# CrowPanel_Pico_Display-2_4_V1_0_240412.net
KiCad netlist of a schematic drawn in EAGLE
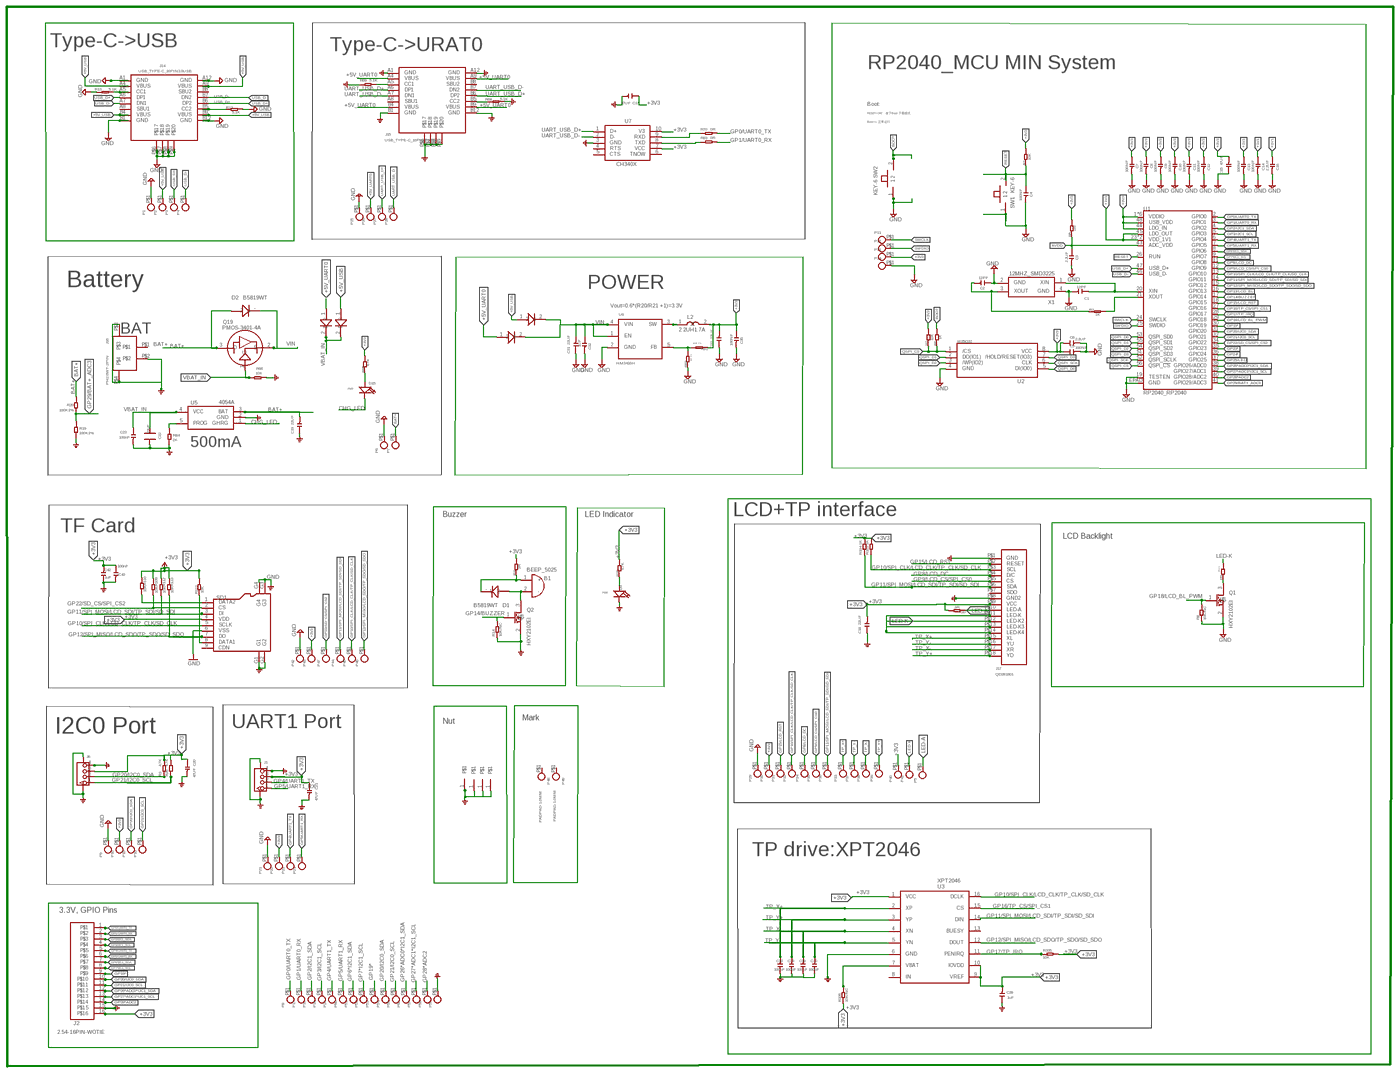
[diagram p0: schematic, sheet 1, overview]
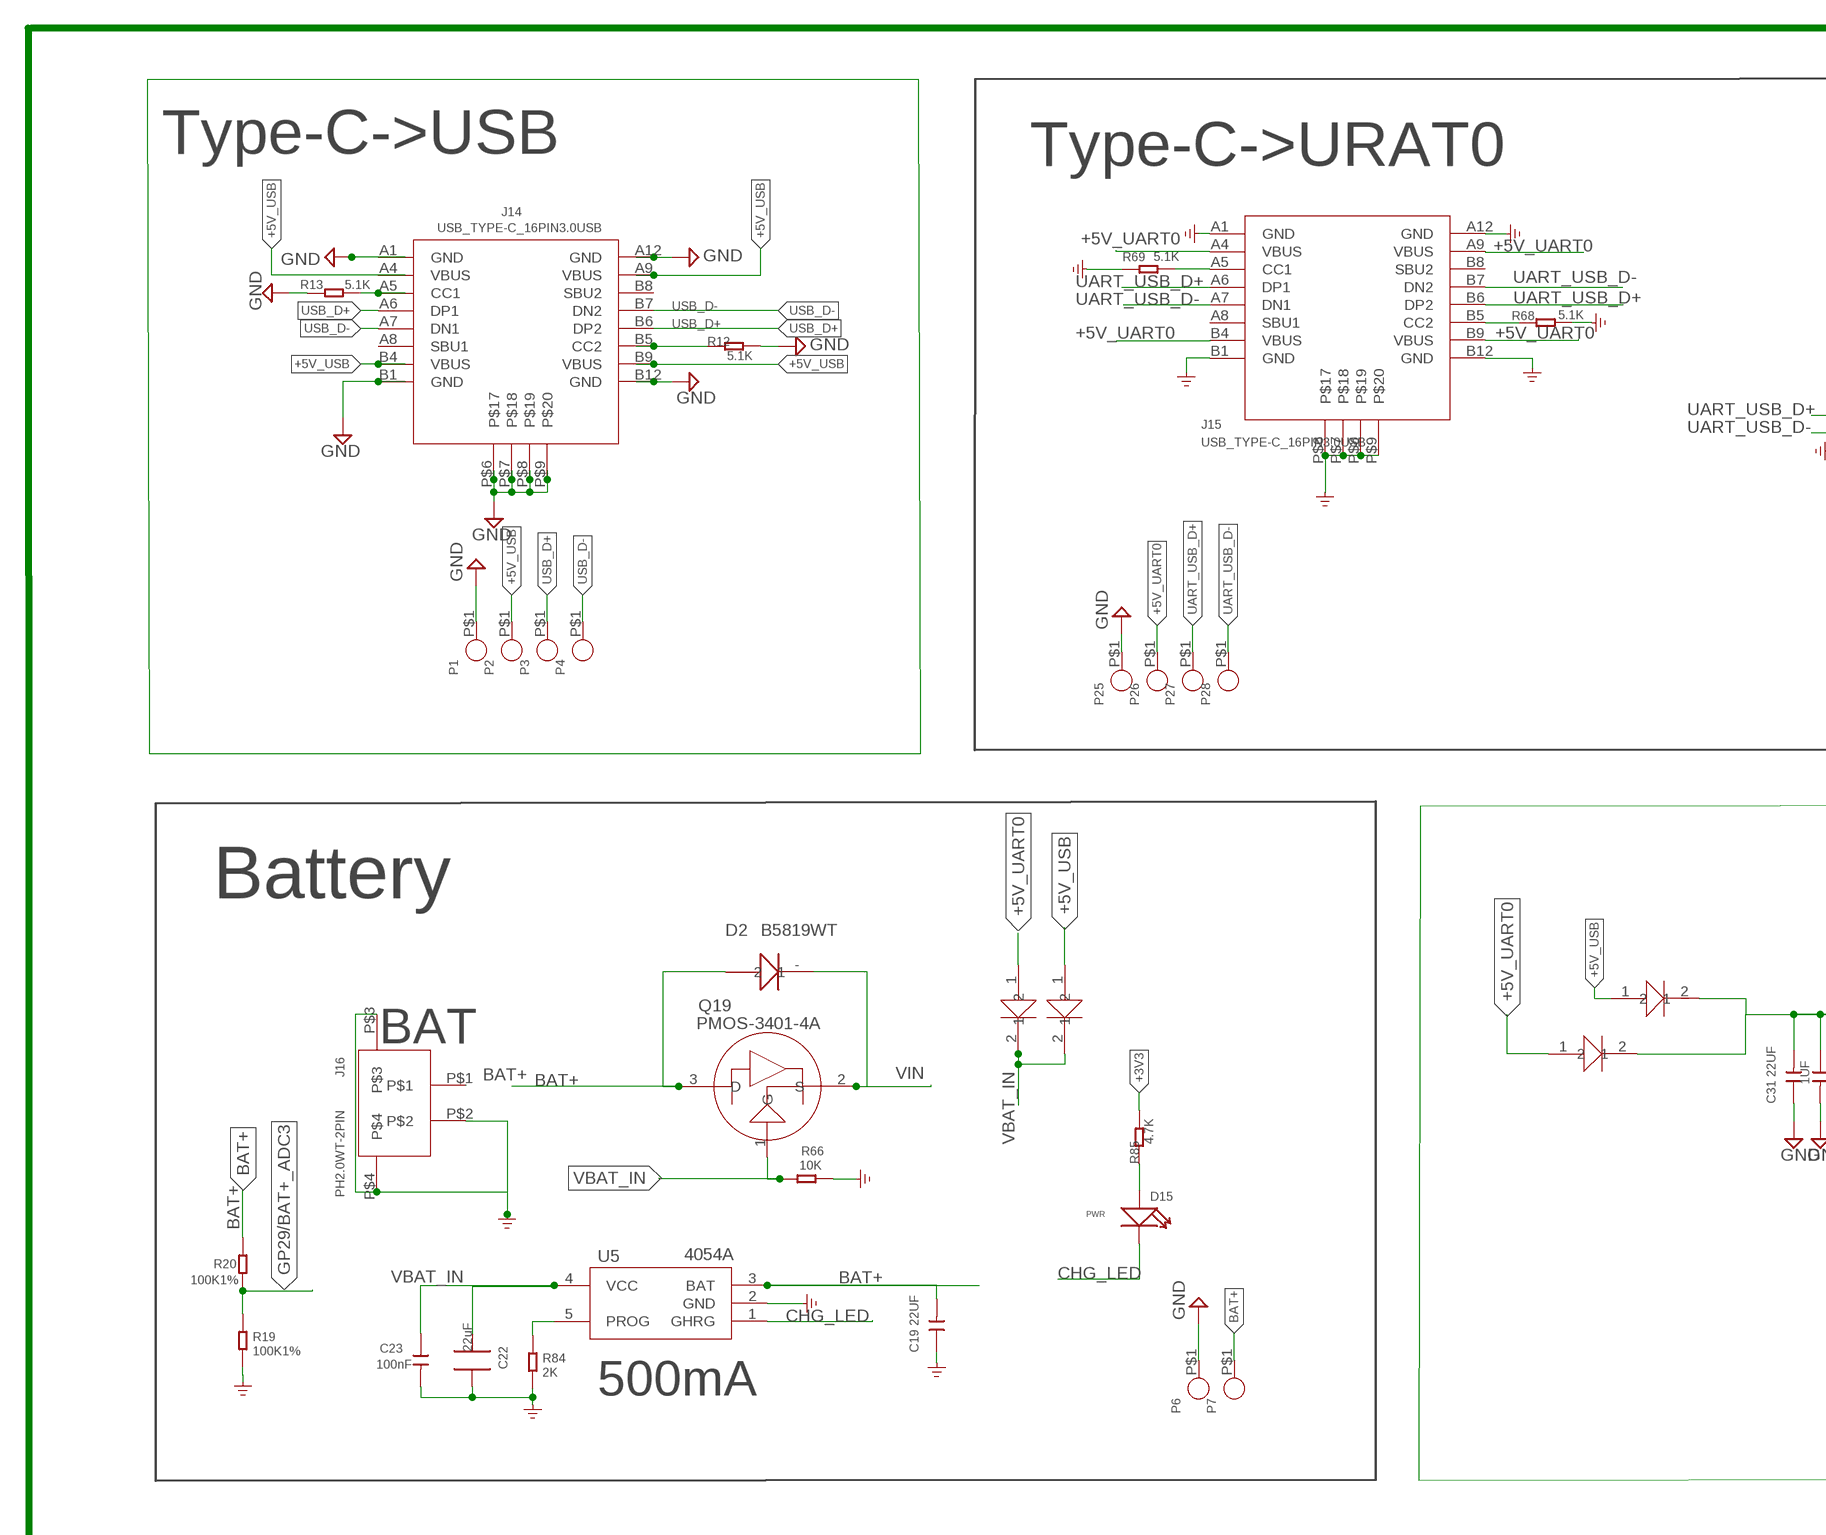
[diagram p1: schematic, sheet 1, part 1 of 4]
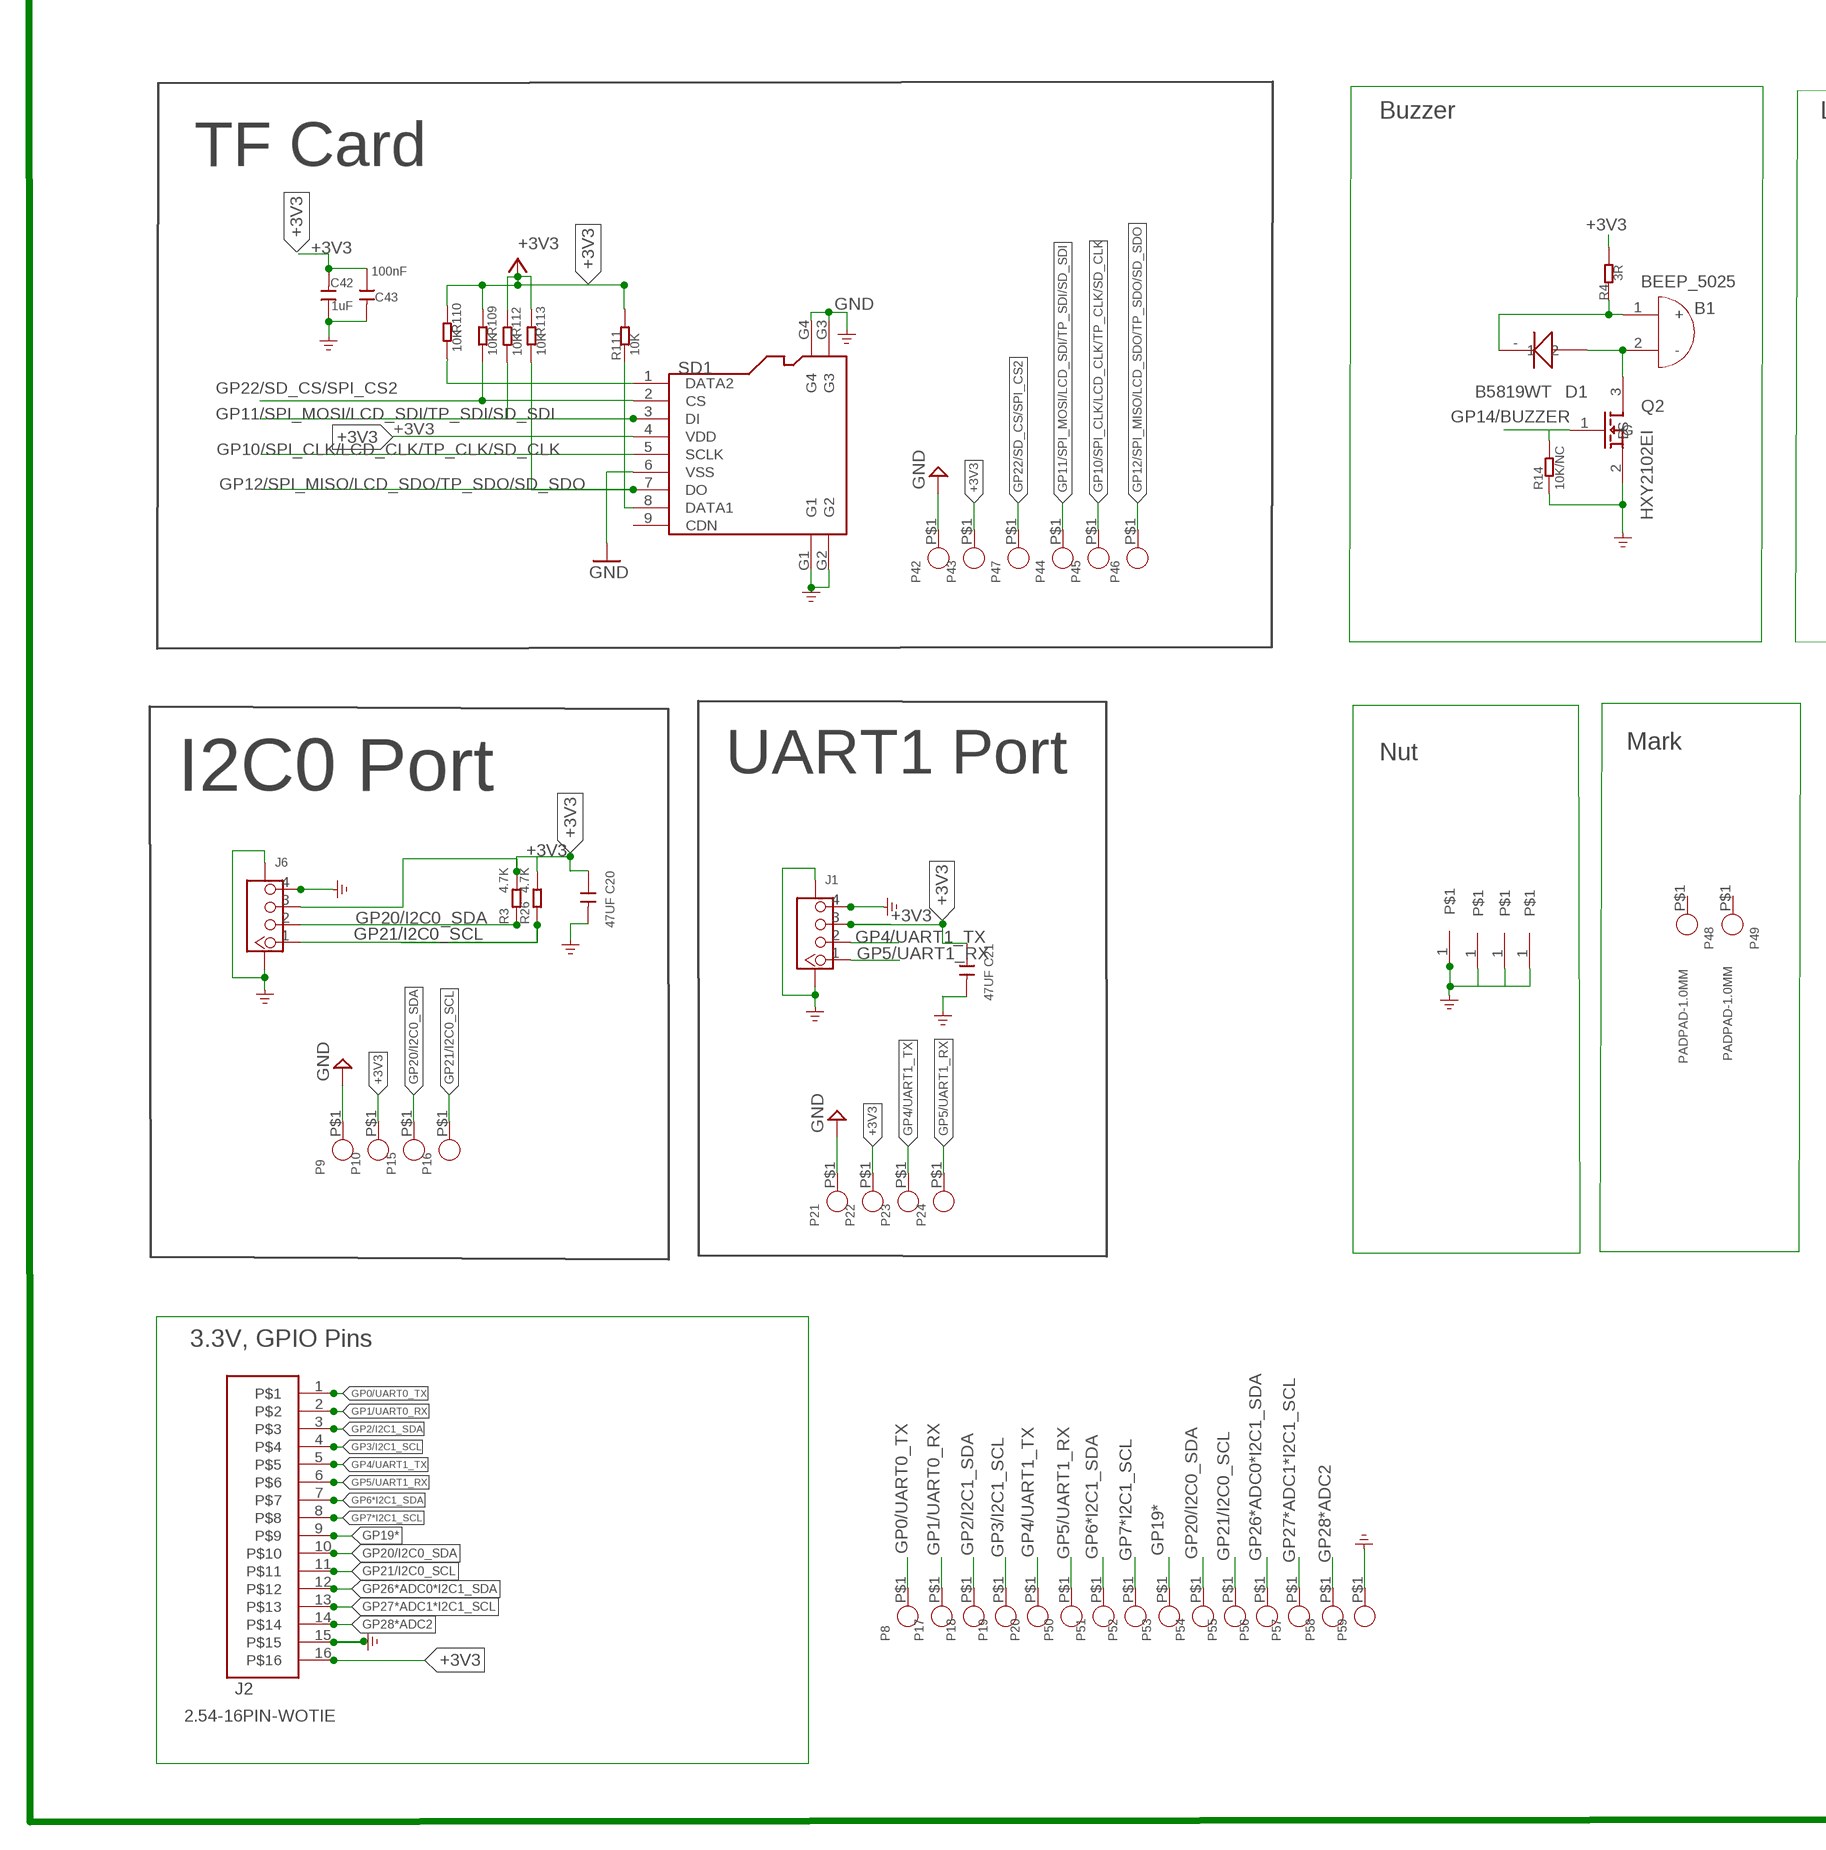
[diagram p2: schematic, sheet 1, part 2 of 4]
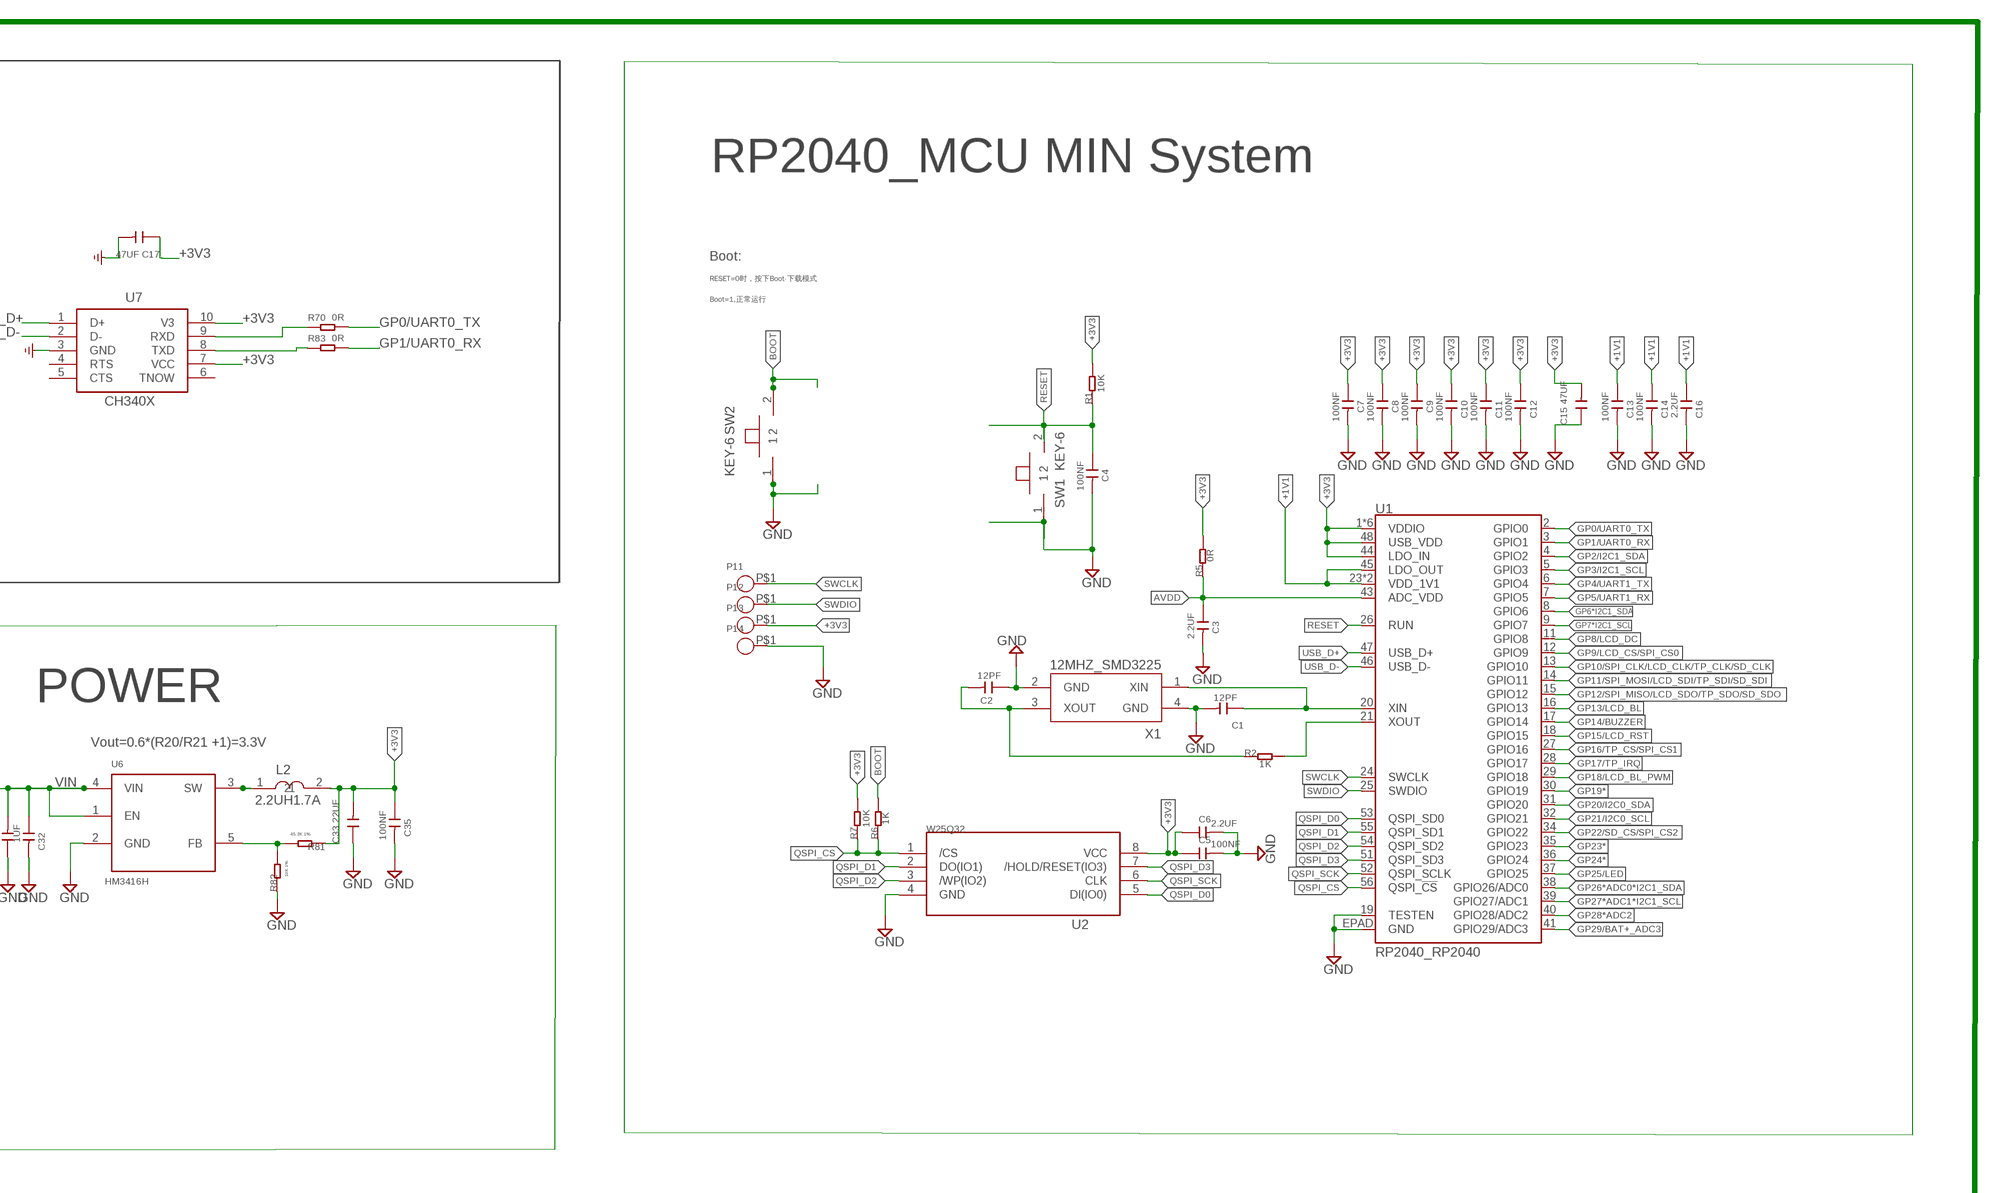
[diagram p3: schematic, sheet 1, part 3 of 4]
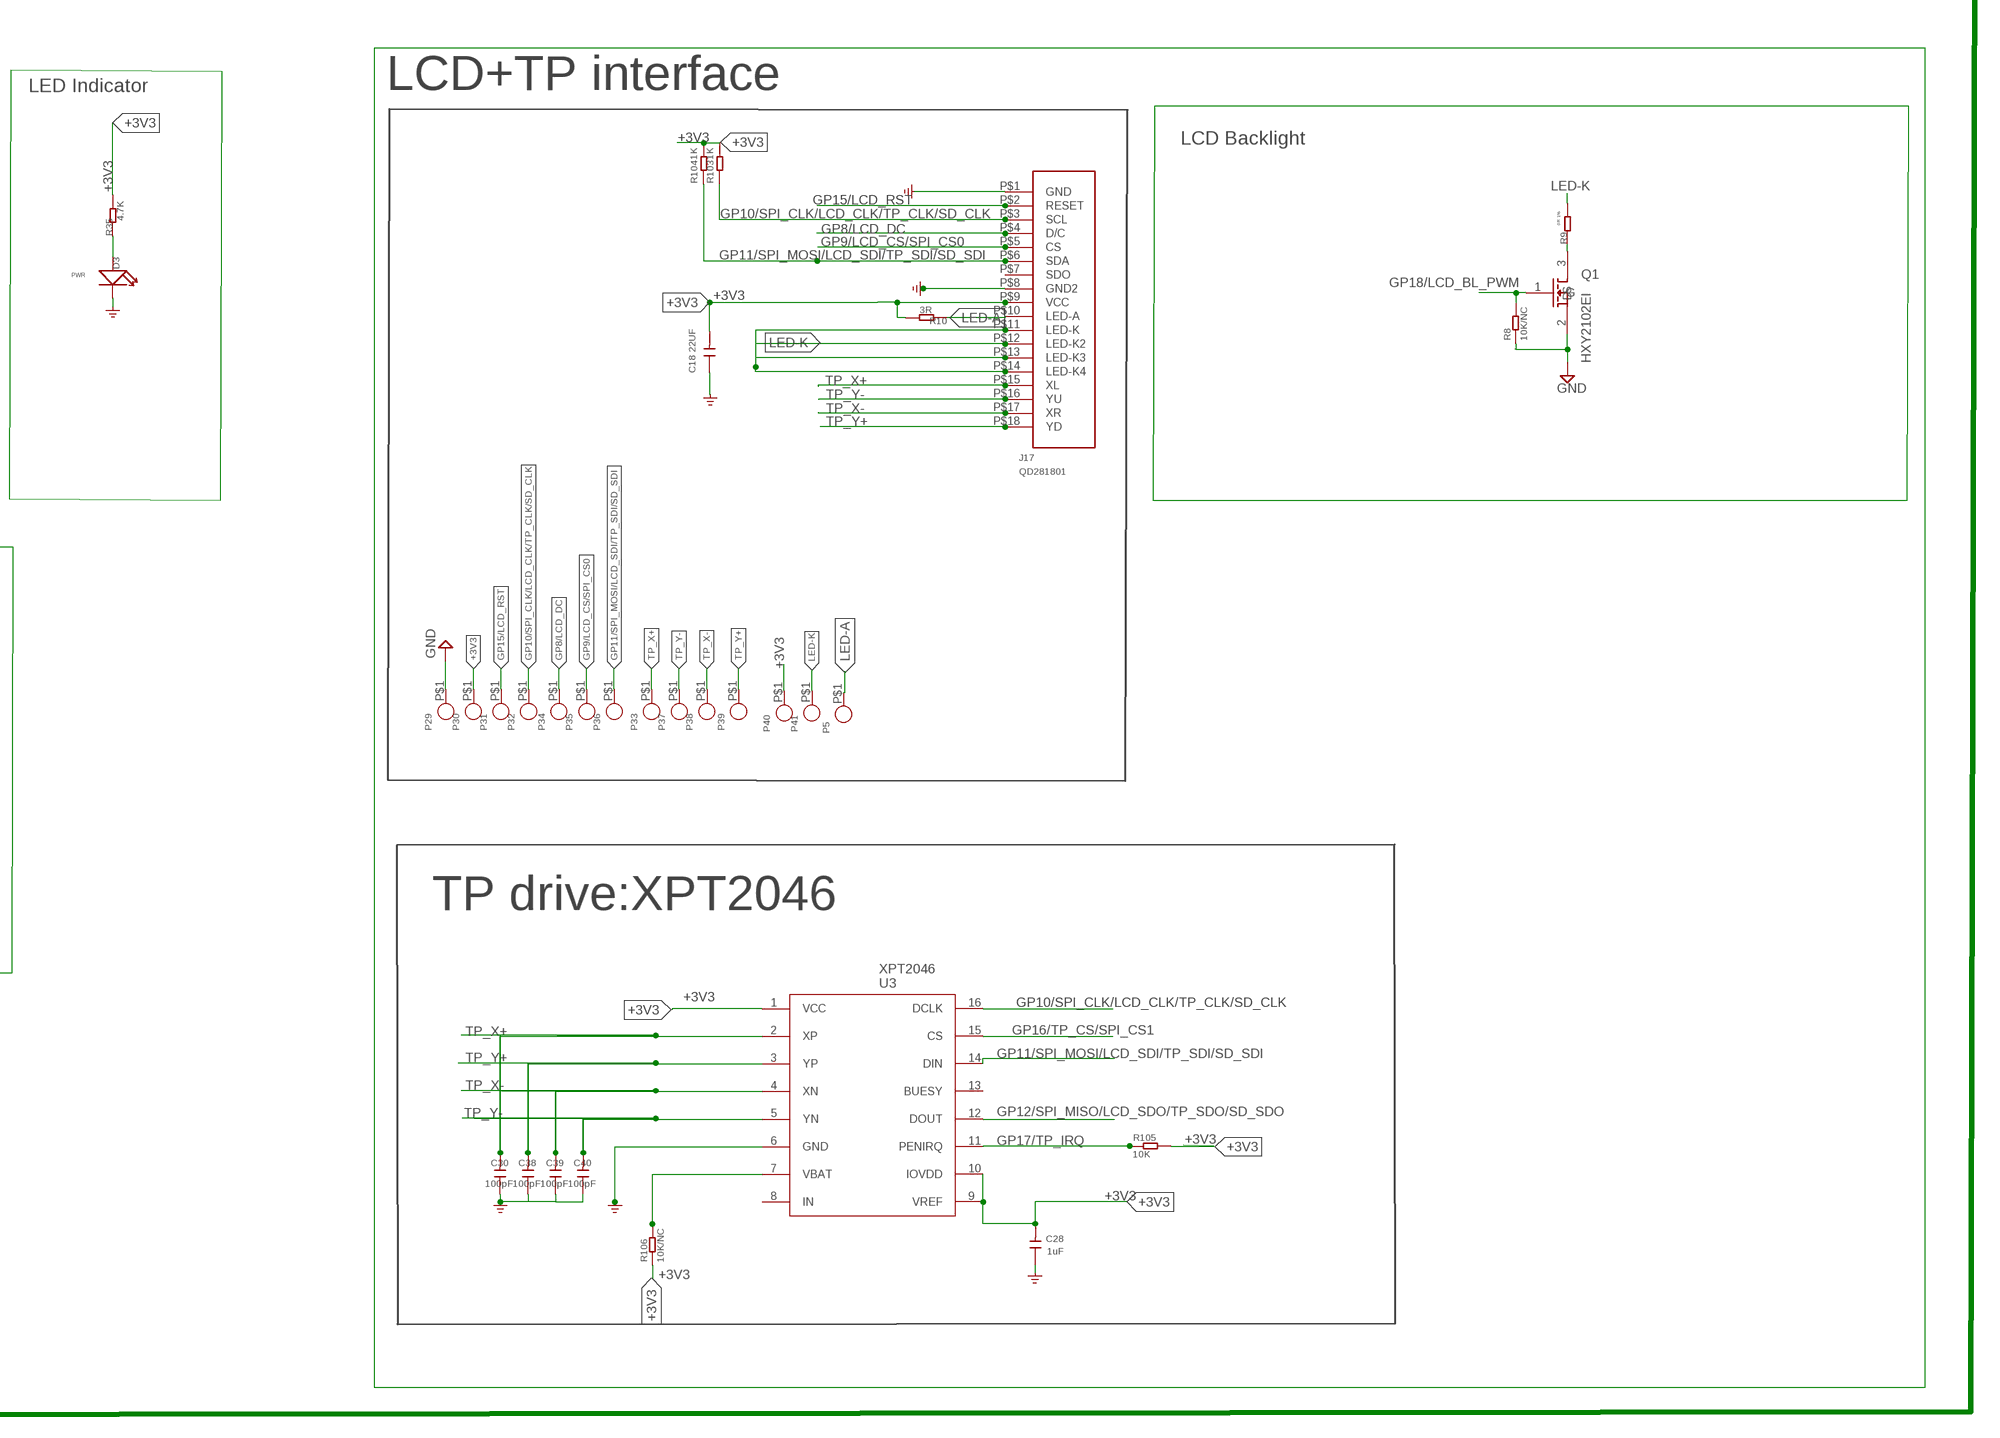
[diagram p4: schematic, sheet 1, part 4 of 4]

(export (version "E")
  (design (tool "Eeschema 10.0.6"))
  (components
    (comp (ref "B1")
      (value "BEEP_5025")
      (footprint "eagle-import:BEEP_5025")
      (libsource (lib "eagle-import") (part "BEEP_5025"))
    )
    (comp (ref "C1")
      (value "12PF")
      (footprint "eagle-import:A_XBJ_0603")
      (libsource (lib "eagle-import") (part "A_XBJ_C0603"))
    )
    (comp (ref "C2")
      (value "12PF")
      (footprint "eagle-import:A_XBJ_0603")
      (libsource (lib "eagle-import") (part "A_XBJ_C0603"))
    )
    (comp (ref "C3")
      (value "2.2UF")
      (footprint "eagle-import:A_XBJ_0603")
      (libsource (lib "eagle-import") (part "A_XBJ_C0603"))
    )
    (comp (ref "C4")
      (value "100NF")
      (footprint "eagle-import:A_XBJ_0603")
      (libsource (lib "eagle-import") (part "A_XBJ_C0603"))
    )
    (comp (ref "C5")
      (value "100NF")
      (footprint "eagle-import:A_XBJ_0603")
      (libsource (lib "eagle-import") (part "A_XBJ_C0603"))
    )
    (comp (ref "C6")
      (value "2.2UF")
      (footprint "eagle-import:A_XBJ_0603")
      (libsource (lib "eagle-import") (part "A_XBJ_C0603"))
    )
    (comp (ref "C7")
      (value "100NF")
      (footprint "eagle-import:A_XBJ_0603")
      (libsource (lib "eagle-import") (part "A_XBJ_C0603"))
    )
    (comp (ref "C8")
      (value "100NF")
      (footprint "eagle-import:A_XBJ_0603")
      (libsource (lib "eagle-import") (part "A_XBJ_C0603"))
    )
    (comp (ref "C9")
      (value "100NF")
      (footprint "eagle-import:A_XBJ_0603")
      (libsource (lib "eagle-import") (part "A_XBJ_C0603"))
    )
    (comp (ref "C10")
      (value "100NF")
      (footprint "eagle-import:A_XBJ_0603")
      (libsource (lib "eagle-import") (part "A_XBJ_C0603"))
    )
    (comp (ref "C11")
      (value "100NF")
      (footprint "eagle-import:A_XBJ_0603")
      (libsource (lib "eagle-import") (part "A_XBJ_C0603"))
    )
    (comp (ref "C12")
      (value "100NF")
      (footprint "eagle-import:A_XBJ_0603")
      (libsource (lib "eagle-import") (part "A_XBJ_C0603"))
    )
    (comp (ref "C13")
      (value "100NF")
      (footprint "eagle-import:A_XBJ_0603")
      (libsource (lib "eagle-import") (part "A_XBJ_C0603"))
    )
    (comp (ref "C14")
      (value "100NF")
      (footprint "eagle-import:A_XBJ_0603")
      (libsource (lib "eagle-import") (part "A_XBJ_C0603"))
    )
    (comp (ref "C15")
      (value "47UF")
      (footprint "eagle-import:A_XBJ_0805")
      (libsource (lib "eagle-import") (part "A_XBJ_C0805"))
    )
    (comp (ref "C16")
      (value "2.2UF")
      (footprint "eagle-import:A_XBJ_0603")
      (libsource (lib "eagle-import") (part "A_XBJ_C0603"))
    )
    (comp (ref "C17")
      (value "47UF")
      (footprint "eagle-import:A_XBJ_0805")
      (libsource (lib "eagle-import") (part "A_XBJ_C0805"))
    )
    (comp (ref "C18")
      (value "22UF")
      (footprint "eagle-import:A_XBJ_0805")
      (libsource (lib "eagle-import") (part "A_XBJ_C0805"))
    )
    (comp (ref "C19")
      (value "22UF")
      (footprint "eagle-import:A_XBJ_0805")
      (libsource (lib "eagle-import") (part "A_XBJ_C0805"))
    )
    (comp (ref "C20")
      (value "47UF")
      (footprint "eagle-import:A_XBJ_0805")
      (libsource (lib "eagle-import") (part "A_XBJ_C0805"))
    )
    (comp (ref "C21")
      (value "47UF")
      (footprint "eagle-import:A_XBJ_0805")
      (libsource (lib "eagle-import") (part "A_XBJ_C0805"))
    )
    (comp (ref "C22")
      (value "22uF")
      (footprint "eagle-import:0805_S")
      (libsource (lib "eagle-import") (part "C0805_S"))
    )
    (comp (ref "C23")
      (value "100nF")
      (footprint "eagle-import:C0603")
      (libsource (lib "eagle-import") (part "C-0603"))
    )
    (comp (ref "C28")
      (value "1uF")
      (footprint "eagle-import:DISCRETE_C0603")
      (libsource (lib "eagle-import") (part "DISCRETE_C-0603"))
    )
    (comp (ref "C30")
      (value "100pF")
      (footprint "eagle-import:0603")
      (libsource (lib "eagle-import") (part "C0603"))
    )
    (comp (ref "C31")
      (value "22UF")
      (footprint "eagle-import:A_XBJ_0805")
      (libsource (lib "eagle-import") (part "A_XBJ_C0805"))
    )
    (comp (ref "C32")
      (value "1UF")
      (footprint "eagle-import:A_XBJ_0603")
      (libsource (lib "eagle-import") (part "A_XBJ_C0603"))
    )
    (comp (ref "C33")
      (value "22UF")
      (footprint "eagle-import:A_XBJ_0805")
      (libsource (lib "eagle-import") (part "A_XBJ_C0805"))
    )
    (comp (ref "C35")
      (value "100NF")
      (footprint "eagle-import:A_XBJ_0603")
      (libsource (lib "eagle-import") (part "A_XBJ_C0603"))
    )
    (comp (ref "C38")
      (value "100pF")
      (footprint "eagle-import:0603")
      (libsource (lib "eagle-import") (part "C0603"))
    )
    (comp (ref "C39")
      (value "100pF")
      (footprint "eagle-import:0603")
      (libsource (lib "eagle-import") (part "C0603"))
    )
    (comp (ref "C40")
      (value "100pF")
      (footprint "eagle-import:0603")
      (libsource (lib "eagle-import") (part "C0603"))
    )
    (comp (ref "C42")
      (value "1uF")
      (footprint "eagle-import:DISCRETE_C0603")
      (libsource (lib "eagle-import") (part "DISCRETE_C-0603"))
    )
    (comp (ref "C43")
      (value "100nF")
      (footprint "eagle-import:C0603")
      (libsource (lib "eagle-import") (part "C-0603"))
    )
    (comp (ref "D1")
      (value "B5819WT")
      (footprint "eagle-import:SOD-523")
      (libsource (lib "eagle-import") (part "DIODE_W"))
    )
    (comp (ref "D2")
      (value "B5819WT")
      (footprint "eagle-import:SOD-523")
      (libsource (lib "eagle-import") (part "DIODE_W"))
    )
    (comp (ref "D3")
      (value "DISCRETE_007-LED0603")
      (footprint "eagle-import:DISCRETE_D0603")
      (libsource (lib "eagle-import") (part "DISCRETE_007-LED0603"))
    )
    (comp (ref "D4")
      (value "SOD-323")
      (footprint "eagle-import:SOD-323")
      (libsource (lib "eagle-import") (part "SOD-323"))
    )
    (comp (ref "D5")
      (value "SOD-323")
      (footprint "eagle-import:SOD-323")
      (libsource (lib "eagle-import") (part "SOD-323"))
    )
    (comp (ref "D6")
      (value "SOD-323")
      (footprint "eagle-import:SOD-323")
      (libsource (lib "eagle-import") (part "SOD-323"))
    )
    (comp (ref "D8")
      (value "SOD-323")
      (footprint "eagle-import:SOD-323")
      (libsource (lib "eagle-import") (part "SOD-323"))
    )
    (comp (ref "D15")
      (value "DISCRETE_007-LED0603")
      (footprint "eagle-import:DISCRETE_D0603")
      (libsource (lib "eagle-import") (part "DISCRETE_007-LED0603"))
    )
    (comp (ref "J1")
      (value "CONNECTOR_TWIG-4P-2.0-SMD-FEMALE-REINFORCE90D")
      (footprint "eagle-import:CONNECTOR_4P-SMD-2.0-90D")
      (libsource (lib "eagle-import") (part "CONNECTOR_TWIG-4P-2.0-SMD-FEMALE-REINFORCE90D"))
    )
    (comp (ref "J2")
      (value "2.54-16PIN-WOTIE")
      (footprint "eagle-import:2.54-16P-WOTIE")
      (libsource (lib "eagle-import") (part "2.54-16PIN-WOTIE"))
    )
    (comp (ref "J6")
      (value "CONNECTOR_TWIG-4P-2.0-SMD-FEMALE-REINFORCE90D")
      (footprint "eagle-import:CONNECTOR_4P-SMD-2.0-90D")
      (libsource (lib "eagle-import") (part "CONNECTOR_TWIG-4P-2.0-SMD-FEMALE-REINFORCE90D"))
    )
    (comp (ref "J14")
      (value "USB_TYPE-C_16PIN3.0USB")
      (footprint "eagle-import:KEVIN_3.0TYPEC-SMD")
      (libsource (lib "eagle-import") (part "USB_TYPE-C_16PIN3.0USB"))
    )
    (comp (ref "J15")
      (value "USB_TYPE-C_16PIN3.0USB")
      (footprint "eagle-import:KEVIN_3.0TYPEC-SMD")
      (libsource (lib "eagle-import") (part "USB_TYPE-C_16PIN3.0USB"))
    )
    (comp (ref "J16")
      (value "PH2.0WT-2PIN")
      (footprint "eagle-import:PH2.0WT-2PIN")
      (libsource (lib "eagle-import") (part "PH2.0WT-2PIN"))
    )
    (comp (ref "J17")
      (value "QD281801")
      (footprint "eagle-import:QD241801-18PIN_0.8")
      (libsource (lib "eagle-import") (part "QD281801"))
    )
    (comp (ref "L2")
      (value "2.2UH1.7A")
      (footprint "eagle-import:0806")
      (libsource (lib "eagle-import") (part "2.2UH1.7A"))
    )
    (comp (ref "P1")
      (value "CROWPI_POW_PADPAD-1.0MM")
      (footprint "eagle-import:CROWPI_POW_PAD-1.0MM")
      (libsource (lib "eagle-import") (part "CROWPI_POW_PADPAD-1.0MM"))
    )
    (comp (ref "P2")
      (value "CROWPI_POW_PADPAD-1.0MM")
      (footprint "eagle-import:CROWPI_POW_PAD-1.0MM")
      (libsource (lib "eagle-import") (part "CROWPI_POW_PADPAD-1.0MM"))
    )
    (comp (ref "P3")
      (value "CROWPI_POW_PADPAD-1.0MM")
      (footprint "eagle-import:CROWPI_POW_PAD-1.0MM")
      (libsource (lib "eagle-import") (part "CROWPI_POW_PADPAD-1.0MM"))
    )
    (comp (ref "P4")
      (value "CROWPI_POW_PADPAD-1.0MM")
      (footprint "eagle-import:CROWPI_POW_PAD-1.0MM")
      (libsource (lib "eagle-import") (part "CROWPI_POW_PADPAD-1.0MM"))
    )
    (comp (ref "P5")
      (value "CROWPI_POW_PADPAD-1.0MM")
      (footprint "eagle-import:CROWPI_POW_PAD-1.0MM")
      (libsource (lib "eagle-import") (part "CROWPI_POW_PADPAD-1.0MM"))
    )
    (comp (ref "P6")
      (value "CROWPI_POW_PADPAD-1.0MM")
      (footprint "eagle-import:CROWPI_POW_PAD-1.0MM")
      (libsource (lib "eagle-import") (part "CROWPI_POW_PADPAD-1.0MM"))
    )
    (comp (ref "P7")
      (value "CROWPI_POW_PADPAD-1.0MM")
      (footprint "eagle-import:CROWPI_POW_PAD-1.0MM")
      (libsource (lib "eagle-import") (part "CROWPI_POW_PADPAD-1.0MM"))
    )
    (comp (ref "P8")
      (value "CROWPI_POW_PADPAD-1.0MM")
      (footprint "eagle-import:CROWPI_POW_PAD-1.0MM")
      (libsource (lib "eagle-import") (part "CROWPI_POW_PADPAD-1.0MM"))
    )
    (comp (ref "P9")
      (value "CROWPI_POW_PADPAD-1.0MM")
      (footprint "eagle-import:CROWPI_POW_PAD-1.0MM")
      (libsource (lib "eagle-import") (part "CROWPI_POW_PADPAD-1.0MM"))
    )
    (comp (ref "P10")
      (value "CROWPI_POW_PADPAD-1.0MM")
      (footprint "eagle-import:CROWPI_POW_PAD-1.0MM")
      (libsource (lib "eagle-import") (part "CROWPI_POW_PADPAD-1.0MM"))
    )
    (comp (ref "P11")
      (value "CROWPI_POW_PADPAD-1.0MM")
      (footprint "eagle-import:CROWPI_POW_PAD-1.0MM")
      (libsource (lib "eagle-import") (part "CROWPI_POW_PADPAD-1.0MM"))
    )
    (comp (ref "P12")
      (value "CROWPI_POW_PADPAD-1.0MM")
      (footprint "eagle-import:CROWPI_POW_PAD-1.0MM")
      (libsource (lib "eagle-import") (part "CROWPI_POW_PADPAD-1.0MM"))
    )
    (comp (ref "P13")
      (value "CROWPI_POW_PADPAD-1.0MM")
      (footprint "eagle-import:CROWPI_POW_PAD-1.0MM")
      (libsource (lib "eagle-import") (part "CROWPI_POW_PADPAD-1.0MM"))
    )
    (comp (ref "P14")
      (value "CROWPI_POW_PADPAD-1.0MM")
      (footprint "eagle-import:CROWPI_POW_PAD-1.0MM")
      (libsource (lib "eagle-import") (part "CROWPI_POW_PADPAD-1.0MM"))
    )
    (comp (ref "P15")
      (value "CROWPI_POW_PADPAD-1.0MM")
      (footprint "eagle-import:CROWPI_POW_PAD-1.0MM")
      (libsource (lib "eagle-import") (part "CROWPI_POW_PADPAD-1.0MM"))
    )
    (comp (ref "P16")
      (value "CROWPI_POW_PADPAD-1.0MM")
      (footprint "eagle-import:CROWPI_POW_PAD-1.0MM")
      (libsource (lib "eagle-import") (part "CROWPI_POW_PADPAD-1.0MM"))
    )
    (comp (ref "P17")
      (value "CROWPI_POW_PADPAD-1.0MM")
      (footprint "eagle-import:CROWPI_POW_PAD-1.0MM")
      (libsource (lib "eagle-import") (part "CROWPI_POW_PADPAD-1.0MM"))
    )
    (comp (ref "P18")
      (value "CROWPI_POW_PADPAD-1.0MM")
      (footprint "eagle-import:CROWPI_POW_PAD-1.0MM")
      (libsource (lib "eagle-import") (part "CROWPI_POW_PADPAD-1.0MM"))
    )
    (comp (ref "P19")
      (value "CROWPI_POW_PADPAD-1.0MM")
      (footprint "eagle-import:CROWPI_POW_PAD-1.0MM")
      (libsource (lib "eagle-import") (part "CROWPI_POW_PADPAD-1.0MM"))
    )
    (comp (ref "P20")
      (value "CROWPI_POW_PADPAD-1.0MM")
      (footprint "eagle-import:CROWPI_POW_PAD-1.0MM")
      (libsource (lib "eagle-import") (part "CROWPI_POW_PADPAD-1.0MM"))
    )
    (comp (ref "P21")
      (value "CROWPI_POW_PADPAD-1.0MM")
      (footprint "eagle-import:CROWPI_POW_PAD-1.0MM")
      (libsource (lib "eagle-import") (part "CROWPI_POW_PADPAD-1.0MM"))
    )
    (comp (ref "P22")
      (value "CROWPI_POW_PADPAD-1.0MM")
      (footprint "eagle-import:CROWPI_POW_PAD-1.0MM")
      (libsource (lib "eagle-import") (part "CROWPI_POW_PADPAD-1.0MM"))
    )
    (comp (ref "P23")
      (value "CROWPI_POW_PADPAD-1.0MM")
      (footprint "eagle-import:CROWPI_POW_PAD-1.0MM")
      (libsource (lib "eagle-import") (part "CROWPI_POW_PADPAD-1.0MM"))
    )
    (comp (ref "P24")
      (value "CROWPI_POW_PADPAD-1.0MM")
      (footprint "eagle-import:CROWPI_POW_PAD-1.0MM")
      (libsource (lib "eagle-import") (part "CROWPI_POW_PADPAD-1.0MM"))
    )
    (comp (ref "P25")
      (value "CROWPI_POW_PADPAD-1.0MM")
      (footprint "eagle-import:CROWPI_POW_PAD-1.0MM")
      (libsource (lib "eagle-import") (part "CROWPI_POW_PADPAD-1.0MM"))
    )
    (comp (ref "P26")
      (value "CROWPI_POW_PADPAD-1.0MM")
      (footprint "eagle-import:CROWPI_POW_PAD-1.0MM")
      (libsource (lib "eagle-import") (part "CROWPI_POW_PADPAD-1.0MM"))
    )
    (comp (ref "P27")
      (value "CROWPI_POW_PADPAD-1.0MM")
      (footprint "eagle-import:CROWPI_POW_PAD-1.0MM")
      (libsource (lib "eagle-import") (part "CROWPI_POW_PADPAD-1.0MM"))
    )
    (comp (ref "P28")
      (value "CROWPI_POW_PADPAD-1.0MM")
      (footprint "eagle-import:CROWPI_POW_PAD-1.0MM")
      (libsource (lib "eagle-import") (part "CROWPI_POW_PADPAD-1.0MM"))
    )
    (comp (ref "P29")
      (value "CROWPI_POW_PADPAD-1.0MM")
      (footprint "eagle-import:CROWPI_POW_PAD-1.0MM")
      (libsource (lib "eagle-import") (part "CROWPI_POW_PADPAD-1.0MM"))
    )
    (comp (ref "P30")
      (value "CROWPI_POW_PADPAD-1.0MM")
      (footprint "eagle-import:CROWPI_POW_PAD-1.0MM")
      (libsource (lib "eagle-import") (part "CROWPI_POW_PADPAD-1.0MM"))
    )
    (comp (ref "P31")
      (value "CROWPI_POW_PADPAD-1.0MM")
      (footprint "eagle-import:CROWPI_POW_PAD-1.0MM")
      (libsource (lib "eagle-import") (part "CROWPI_POW_PADPAD-1.0MM"))
    )
    (comp (ref "P32")
      (value "CROWPI_POW_PADPAD-1.0MM")
      (footprint "eagle-import:CROWPI_POW_PAD-1.0MM")
      (libsource (lib "eagle-import") (part "CROWPI_POW_PADPAD-1.0MM"))
    )
    (comp (ref "P33")
      (value "CROWPI_POW_PADPAD-1.0MM")
      (footprint "eagle-import:CROWPI_POW_PAD-1.0MM")
      (libsource (lib "eagle-import") (part "CROWPI_POW_PADPAD-1.0MM"))
    )
    (comp (ref "P34")
      (value "CROWPI_POW_PADPAD-1.0MM")
      (footprint "eagle-import:CROWPI_POW_PAD-1.0MM")
      (libsource (lib "eagle-import") (part "CROWPI_POW_PADPAD-1.0MM"))
    )
    (comp (ref "P35")
      (value "CROWPI_POW_PADPAD-1.0MM")
      (footprint "eagle-import:CROWPI_POW_PAD-1.0MM")
      (libsource (lib "eagle-import") (part "CROWPI_POW_PADPAD-1.0MM"))
    )
    (comp (ref "P36")
      (value "CROWPI_POW_PADPAD-1.0MM")
      (footprint "eagle-import:CROWPI_POW_PAD-1.0MM")
      (libsource (lib "eagle-import") (part "CROWPI_POW_PADPAD-1.0MM"))
    )
    (comp (ref "P37")
      (value "CROWPI_POW_PADPAD-1.0MM")
      (footprint "eagle-import:CROWPI_POW_PAD-1.0MM")
      (libsource (lib "eagle-import") (part "CROWPI_POW_PADPAD-1.0MM"))
    )
    (comp (ref "P38")
      (value "CROWPI_POW_PADPAD-1.0MM")
      (footprint "eagle-import:CROWPI_POW_PAD-1.0MM")
      (libsource (lib "eagle-import") (part "CROWPI_POW_PADPAD-1.0MM"))
    )
    (comp (ref "P39")
      (value "CROWPI_POW_PADPAD-1.0MM")
      (footprint "eagle-import:CROWPI_POW_PAD-1.0MM")
      (libsource (lib "eagle-import") (part "CROWPI_POW_PADPAD-1.0MM"))
    )
    (comp (ref "P40")
      (value "CROWPI_POW_PADPAD-1.0MM")
      (footprint "eagle-import:CROWPI_POW_PAD-1.0MM")
      (libsource (lib "eagle-import") (part "CROWPI_POW_PADPAD-1.0MM"))
    )
    (comp (ref "P41")
      (value "CROWPI_POW_PADPAD-1.0MM")
      (footprint "eagle-import:CROWPI_POW_PAD-1.0MM")
      (libsource (lib "eagle-import") (part "CROWPI_POW_PADPAD-1.0MM"))
    )
    (comp (ref "P42")
      (value "CROWPI_POW_PADPAD-1.0MM")
      (footprint "eagle-import:CROWPI_POW_PAD-1.0MM")
      (libsource (lib "eagle-import") (part "CROWPI_POW_PADPAD-1.0MM"))
    )
    (comp (ref "P43")
      (value "CROWPI_POW_PADPAD-1.0MM")
      (footprint "eagle-import:CROWPI_POW_PAD-1.0MM")
      (libsource (lib "eagle-import") (part "CROWPI_POW_PADPAD-1.0MM"))
    )
    (comp (ref "P44")
      (value "CROWPI_POW_PADPAD-1.0MM")
      (footprint "eagle-import:CROWPI_POW_PAD-1.0MM")
      (libsource (lib "eagle-import") (part "CROWPI_POW_PADPAD-1.0MM"))
    )
    (comp (ref "P45")
      (value "CROWPI_POW_PADPAD-1.0MM")
      (footprint "eagle-import:CROWPI_POW_PAD-1.0MM")
      (libsource (lib "eagle-import") (part "CROWPI_POW_PADPAD-1.0MM"))
    )
    (comp (ref "P46")
      (value "CROWPI_POW_PADPAD-1.0MM")
      (footprint "eagle-import:CROWPI_POW_PAD-1.0MM")
      (libsource (lib "eagle-import") (part "CROWPI_POW_PADPAD-1.0MM"))
    )
    (comp (ref "P47")
      (value "CROWPI_POW_PADPAD-1.0MM")
      (footprint "eagle-import:CROWPI_POW_PAD-1.0MM")
      (libsource (lib "eagle-import") (part "CROWPI_POW_PADPAD-1.0MM"))
    )
    (comp (ref "P48")
      (value "PADPAD-1.0MM")
      (footprint "eagle-import:PAD-1.0MM")
      (libsource (lib "eagle-import") (part "PADPAD-1.0MM"))
    )
    (comp (ref "P49")
      (value "PADPAD-1.0MM")
      (footprint "eagle-import:PAD-1.0MM")
      (libsource (lib "eagle-import") (part "PADPAD-1.0MM"))
    )
    (comp (ref "P50")
      (value "CROWPI_POW_PADPAD-1.0MM")
      (footprint "eagle-import:CROWPI_POW_PAD-1.0MM")
      (libsource (lib "eagle-import") (part "CROWPI_POW_PADPAD-1.0MM"))
    )
    (comp (ref "P51")
      (value "CROWPI_POW_PADPAD-1.0MM")
      (footprint "eagle-import:CROWPI_POW_PAD-1.0MM")
      (libsource (lib "eagle-import") (part "CROWPI_POW_PADPAD-1.0MM"))
    )
    (comp (ref "P52")
      (value "CROWPI_POW_PADPAD-1.0MM")
      (footprint "eagle-import:CROWPI_POW_PAD-1.0MM")
      (libsource (lib "eagle-import") (part "CROWPI_POW_PADPAD-1.0MM"))
    )
    (comp (ref "P53")
      (value "CROWPI_POW_PADPAD-1.0MM")
      (footprint "eagle-import:CROWPI_POW_PAD-1.0MM")
      (libsource (lib "eagle-import") (part "CROWPI_POW_PADPAD-1.0MM"))
    )
    (comp (ref "P54")
      (value "CROWPI_POW_PADPAD-1.0MM")
      (footprint "eagle-import:CROWPI_POW_PAD-1.0MM")
      (libsource (lib "eagle-import") (part "CROWPI_POW_PADPAD-1.0MM"))
    )
    (comp (ref "P55")
      (value "CROWPI_POW_PADPAD-1.0MM")
      (footprint "eagle-import:CROWPI_POW_PAD-1.0MM")
      (libsource (lib "eagle-import") (part "CROWPI_POW_PADPAD-1.0MM"))
    )
    (comp (ref "P56")
      (value "CROWPI_POW_PADPAD-1.0MM")
      (footprint "eagle-import:CROWPI_POW_PAD-1.0MM")
      (libsource (lib "eagle-import") (part "CROWPI_POW_PADPAD-1.0MM"))
    )
    (comp (ref "P57")
      (value "CROWPI_POW_PADPAD-1.0MM")
      (footprint "eagle-import:CROWPI_POW_PAD-1.0MM")
      (libsource (lib "eagle-import") (part "CROWPI_POW_PADPAD-1.0MM"))
    )
    (comp (ref "P58")
      (value "CROWPI_POW_PADPAD-1.0MM")
      (footprint "eagle-import:CROWPI_POW_PAD-1.0MM")
      (libsource (lib "eagle-import") (part "CROWPI_POW_PADPAD-1.0MM"))
    )
    (comp (ref "P59")
      (value "CROWPI_POW_PADPAD-1.0MM")
      (footprint "eagle-import:CROWPI_POW_PAD-1.0MM")
      (libsource (lib "eagle-import") (part "CROWPI_POW_PADPAD-1.0MM"))
    )
    (comp (ref "Q1")
      (value "HXY2102EI")
      (footprint "eagle-import:SOT-323_W")
      (libsource (lib "eagle-import") (part "HXY2102EI"))
    )
    (comp (ref "Q2")
      (value "HXY2102EI")
      (footprint "eagle-import:SOT-323_W")
      (libsource (lib "eagle-import") (part "HXY2102EI"))
    )
    (comp (ref "Q19")
      (value "PMOS-3401-4A")
      (footprint "eagle-import:SOT-23")
      (libsource (lib "eagle-import") (part "P-MOS-SOT23"))
    )
    (comp (ref "R1")
      (value "10K")
      (footprint "eagle-import:DISCRETE_R0603")
      (libsource (lib "eagle-import") (part "Lora_RA-08H_Dev_DISCRETE_R-0603"))
    )
    (comp (ref "R2")
      (value "1K")
      (footprint "eagle-import:DISCRETE_R0603")
      (libsource (lib "eagle-import") (part "Lora_RA-08H_Dev_DISCRETE_R-0603"))
    )
    (comp (ref "R3")
      (value "4.7K")
      (footprint "eagle-import:DISCRETE_R0603")
      (libsource (lib "eagle-import") (part "Crowtail-_LED-V2.0-20190615-01_DISCRETE_R-0603"))
    )
    (comp (ref "R4")
      (value "3R")
      (footprint "eagle-import:DISCRETE_R0603")
      (libsource (lib "eagle-import") (part "Lora_RA-08H_Dev_DISCRETE_R-0603"))
    )
    (comp (ref "R5")
      (value "0R")
      (footprint "eagle-import:DISCRETE_R0603")
      (libsource (lib "eagle-import") (part "Lora_RA-08H_Dev_DISCRETE_R-0603"))
    )
    (comp (ref "R6")
      (value "1K")
      (footprint "eagle-import:DISCRETE_R0603")
      (libsource (lib "eagle-import") (part "Lora_RA-08H_Dev_DISCRETE_R-0603"))
    )
    (comp (ref "R7")
      (value "10K")
      (footprint "eagle-import:DISCRETE_R0603")
      (libsource (lib "eagle-import") (part "Lora_RA-08H_Dev_DISCRETE_R-0603"))
    )
    (comp (ref "R8")
      (value "10K/NC")
      (footprint "eagle-import:DISCRETE_R0603")
      (libsource (lib "eagle-import") (part "DISCRETE_R-0603"))
    )
    (comp (ref "R9")
      (value "0R 1%")
      (footprint "eagle-import:DISCRETE_R0603")
      (libsource (lib "eagle-import") (part "Lora_RA-08H_Dev_DISCRETE_R-0603"))
    )
    (comp (ref "R10")
      (value "3R")
      (footprint "eagle-import:DISCRETE_R0603")
      (libsource (lib "eagle-import") (part "Lora_RA-08H_Dev_DISCRETE_R-0603"))
    )
    (comp (ref "R12")
      (value "5.1K")
      (footprint "eagle-import:DISCRETE_R0603")
      (libsource (lib "eagle-import") (part "Lora_RA-08H_Dev_DISCRETE_R-0603"))
    )
    (comp (ref "R13")
      (value "5.1K")
      (footprint "eagle-import:DISCRETE_R0603")
      (libsource (lib "eagle-import") (part "Lora_RA-08H_Dev_DISCRETE_R-0603"))
    )
    (comp (ref "R14")
      (value "10K/NC")
      (footprint "eagle-import:DISCRETE_R0603")
      (libsource (lib "eagle-import") (part "DISCRETE_R-0603"))
    )
    (comp (ref "R19")
      (value "100K1%")
      (footprint "eagle-import:DISCRETE_R0603")
      (libsource (lib "eagle-import") (part "DISCRETE_R-0603"))
    )
    (comp (ref "R20")
      (value "100K1%")
      (footprint "eagle-import:DISCRETE_R0603")
      (libsource (lib "eagle-import") (part "DISCRETE_R-0603"))
    )
    (comp (ref "R26")
      (value "4.7K")
      (footprint "eagle-import:DISCRETE_R0603")
      (libsource (lib "eagle-import") (part "Crowtail-_LED-V2.0-20190615-01_DISCRETE_R-0603"))
    )
    (comp (ref "R35")
      (value "4.7K")
      (footprint "eagle-import:DISCRETE_R0603")
      (libsource (lib "eagle-import") (part "Lora_RA-08H_Dev_DISCRETE_R-0603"))
    )
    (comp (ref "R66")
      (value "10K")
      (footprint "eagle-import:DISCRETE_R0603")
      (libsource (lib "eagle-import") (part "DISCRETE_R-0603"))
    )
    (comp (ref "R68")
      (value "5.1K")
      (footprint "eagle-import:DISCRETE_R0603")
      (libsource (lib "eagle-import") (part "Crowtail-_LED-V2.0-20190615-01_DISCRETE_R-0603"))
    )
    (comp (ref "R69")
      (value "5.1K")
      (footprint "eagle-import:DISCRETE_R0603")
      (libsource (lib "eagle-import") (part "Crowtail-_LED-V2.0-20190615-01_DISCRETE_R-0603"))
    )
    (comp (ref "R70")
      (value "0R")
      (footprint "eagle-import:DISCRETE_R0603")
      (libsource (lib "eagle-import") (part "Crowtail-_LED-V2.0-20190615-01_DISCRETE_R-0603"))
    )
    (comp (ref "R81")
      (value "45.3K 1%")
      (footprint "eagle-import:DISCRETE_R0603")
      (libsource (lib "eagle-import") (part "Lora_RA-08H_Dev_DISCRETE_R-0603"))
    )
    (comp (ref "R82")
      (value "10K 1%")
      (footprint "eagle-import:DISCRETE_R0603")
      (libsource (lib "eagle-import") (part "Lora_RA-08H_Dev_DISCRETE_R-0603"))
    )
    (comp (ref "R83")
      (value "0R")
      (footprint "eagle-import:DISCRETE_R0603")
      (libsource (lib "eagle-import") (part "Crowtail-_LED-V2.0-20190615-01_DISCRETE_R-0603"))
    )
    (comp (ref "R84")
      (value "2K")
      (footprint "eagle-import:DISCRETE_R0603")
      (libsource (lib "eagle-import") (part "DISCRETE_R-0603"))
    )
    (comp (ref "R85")
      (value "4.7K")
      (footprint "eagle-import:DISCRETE_R0603")
      (libsource (lib "eagle-import") (part "Lora_RA-08H_Dev_DISCRETE_R-0603"))
    )
    (comp (ref "R103")
      (value "1K")
      (footprint "eagle-import:DISCRETE_R0603")
      (libsource (lib "eagle-import") (part "Crowtail-_LED-V2.0-20190615-01_DISCRETE_R-0603"))
    )
    (comp (ref "R104")
      (value "1K")
      (footprint "eagle-import:DISCRETE_R0603")
      (libsource (lib "eagle-import") (part "Crowtail-_LED-V2.0-20190615-01_DISCRETE_R-0603"))
    )
    (comp (ref "R105")
      (value "10K")
      (footprint "eagle-import:DISCRETE_R0603")
      (libsource (lib "eagle-import") (part "DISCRETE_R-0603"))
    )
    (comp (ref "R106")
      (value "10K/NC")
      (footprint "eagle-import:DISCRETE_R0603")
      (libsource (lib "eagle-import") (part "DISCRETE_R-0603"))
    )
    (comp (ref "R109")
      (value "10K")
      (footprint "eagle-import:DISCRETE_R0603")
      (libsource (lib "eagle-import") (part "Crowtail-_LED-V2.0-20190615-01_DISCRETE_R-0603"))
    )
    (comp (ref "R110")
      (value "10K")
      (footprint "eagle-import:DISCRETE_R0603")
      (libsource (lib "eagle-import") (part "Crowtail-_LED-V2.0-20190615-01_DISCRETE_R-0603"))
    )
    (comp (ref "R111")
      (value "10K")
      (footprint "eagle-import:DISCRETE_R0603")
      (libsource (lib "eagle-import") (part "Crowtail-_LED-V2.0-20190615-01_DISCRETE_R-0603"))
    )
    (comp (ref "R112")
      (value "10K")
      (footprint "eagle-import:DISCRETE_R0603")
      (libsource (lib "eagle-import") (part "Crowtail-_LED-V2.0-20190615-01_DISCRETE_R-0603"))
    )
    (comp (ref "R113")
      (value "10K")
      (footprint "eagle-import:DISCRETE_R0603")
      (libsource (lib "eagle-import") (part "Crowtail-_LED-V2.0-20190615-01_DISCRETE_R-0603"))
    )
    (comp (ref "SD1")
      (value "HOLDER-MICROSD-9P")
      (footprint "eagle-import:9P-SMD-W_-RING")
      (libsource (lib "eagle-import") (part "HOLDER-MICROSD-9P"))
    )
    (comp (ref "SW1")
      (value "KEY-6")
      (footprint "eagle-import:KEY-6")
      (libsource (lib "eagle-import") (part "KEY-6"))
    )
    (comp (ref "SW2")
      (value "KEY-6")
      (footprint "eagle-import:KEY-6")
      (libsource (lib "eagle-import") (part "KEY-6"))
    )
    (comp (ref "T1")
      (value "3M-5")
      (footprint "eagle-import:3M-5")
      (libsource (lib "eagle-import") (part "3M-5"))
    )
    (comp (ref "T2")
      (value "3M-5")
      (footprint "eagle-import:3M-5")
      (libsource (lib "eagle-import") (part "3M-5"))
    )
    (comp (ref "T3")
      (value "3M-5")
      (footprint "eagle-import:3M-5")
      (libsource (lib "eagle-import") (part "3M-5"))
    )
    (comp (ref "T4")
      (value "3M-5")
      (footprint "eagle-import:3M-5")
      (libsource (lib "eagle-import") (part "3M-5"))
    )
    (comp (ref "U1")
      (value "RP2040_RP2040")
      (footprint "eagle-import:RP2040_QFN-56")
      (libsource (lib "eagle-import") (part "RP2040_RP2040"))
    )
    (comp (ref "U2")
      (value "SELF_W25Q128JV")
      (footprint "eagle-import:SELF_SOIC-8-208MIL")
      (libsource (lib "eagle-import") (part "SELF_W25Q128JV"))
    )
    (comp (ref "U3")
      (value "XPT2046")
      (footprint "eagle-import:XP2046-SSOP16")
      (libsource (lib "eagle-import") (part "XPT2046"))
    )
    (comp (ref "U5")
      (value "4054A")
      (footprint "eagle-import:SOP23-5")
      (libsource (lib "eagle-import") (part "4054A"))
    )
    (comp (ref "U6")
      (value "HM3416H")
      (footprint "eagle-import:CROWBOT_-V1.0-20220525_A_XBJ_SOT23-5")
      (libsource (lib "eagle-import") (part "CROWBOT_-V1.0-20220525_A_XBJ_HM3420B"))
    )
    (comp (ref "U7")
      (value "CH340X")
      (footprint "eagle-import:MSOP-10_W")
      (libsource (lib "eagle-import") (part "CH340E"))
    )
    (comp (ref "X1")
      (value "12MHZ_SMD3225")
      (footprint "eagle-import:A_XBJ_SMD3225")
      (libsource (lib "eagle-import") (part "A_XBJ_XTAL"))
    )
  )
  (nets
    (net (code "1") (name "+1V1") (class "Default")
      (node (ref "C13") (pin "1") (pinfunction "1_1") (pintype "passive"))
      (node (ref "C14") (pin "1") (pinfunction "1_1") (pintype "passive"))
      (node (ref "C16") (pin "1") (pinfunction "1_1") (pintype "passive"))
      (node (ref "U1") (pin "23") (pinfunction "VDD_1V1_23") (pintype "bidirectional"))
      (node (ref "U1") (pin "45") (pinfunction "LDO_OUT_45") (pintype "bidirectional"))
      (node (ref "U1") (pin "50") (pinfunction "VDD_1V1_50") (pintype "bidirectional"))
    )
    (net (code "2") (name "+3V3") (class "Default")
      (node (ref "C10") (pin "1") (pinfunction "1_1") (pintype "passive"))
      (node (ref "C11") (pin "1") (pinfunction "1_1") (pintype "passive"))
      (node (ref "C12") (pin "1") (pinfunction "1_1") (pintype "passive"))
      (node (ref "C15") (pin "2") (pinfunction "2_2") (pintype "passive"))
      (node (ref "C17") (pin "1") (pinfunction "1_1") (pintype "passive"))
      (node (ref "C18") (pin "2") (pinfunction "2_2") (pintype "passive"))
      (node (ref "C20") (pin "1") (pinfunction "1_1") (pintype "passive"))
      (node (ref "C21") (pin "1") (pinfunction "1_1") (pintype "passive"))
      (node (ref "C28") (pin "2") (pinfunction "2_2") (pintype "passive"))
      (node (ref "C33") (pin "2") (pinfunction "2_2") (pintype "passive"))
      (node (ref "C35") (pin "1") (pinfunction "1_1") (pintype "passive"))
      (node (ref "C42") (pin "2") (pinfunction "2_2") (pintype "passive"))
      (node (ref "C43") (pin "1") (pinfunction "1_1") (pintype "passive"))
      (node (ref "C5") (pin "1") (pinfunction "1_1") (pintype "passive"))
      (node (ref "C6") (pin "1") (pinfunction "1_1") (pintype "passive"))
      (node (ref "C7") (pin "1") (pinfunction "1_1") (pintype "passive"))
      (node (ref "C8") (pin "1") (pinfunction "1_1") (pintype "passive"))
      (node (ref "C9") (pin "1") (pinfunction "1_1") (pintype "passive"))
      (node (ref "J1") (pin "3") (pinfunction "3_3") (pintype "bidirectional"))
      (node (ref "J17") (pin "P$9") (pinfunction "VCC_P$9") (pintype "bidirectional"))
      (node (ref "J2") (pin "16") (pinfunction "P$16_16") (pintype "bidirectional"))
      (node (ref "J6") (pin "3") (pinfunction "3_3") (pintype "bidirectional"))
      (node (ref "L2") (pin "2") (pinfunction "2_2") (pintype "bidirectional"))
      (node (ref "P10") (pin "P$1") (pinfunction "P$1_P$1") (pintype "bidirectional"))
      (node (ref "P13") (pin "P$1") (pinfunction "P$1_P$1") (pintype "bidirectional"))
      (node (ref "P22") (pin "P$1") (pinfunction "P$1_P$1") (pintype "bidirectional"))
      (node (ref "P30") (pin "P$1") (pinfunction "P$1_P$1") (pintype "bidirectional"))
      (node (ref "P40") (pin "P$1") (pinfunction "P$1_P$1") (pintype "bidirectional"))
      (node (ref "P43") (pin "P$1") (pinfunction "P$1_P$1") (pintype "bidirectional"))
      (node (ref "R1") (pin "2") (pinfunction "2_2") (pintype "passive"))
      (node (ref "R10") (pin "2") (pinfunction "2_2") (pintype "passive"))
      (node (ref "R103") (pin "2") (pinfunction "2_2") (pintype "passive"))
      (node (ref "R104") (pin "2") (pinfunction "2_2") (pintype "passive"))
      (node (ref "R105") (pin "2") (pinfunction "2_2") (pintype "passive"))
      (node (ref "R106") (pin "1") (pinfunction "1_1") (pintype "passive"))
      (node (ref "R109") (pin "1") (pinfunction "1_1") (pintype "passive"))
      (node (ref "R110") (pin "1") (pinfunction "1_1") (pintype "passive"))
      (node (ref "R111") (pin "1") (pinfunction "1_1") (pintype "passive"))
      (node (ref "R112") (pin "1") (pinfunction "1_1") (pintype "passive"))
      (node (ref "R113") (pin "1") (pinfunction "1_1") (pintype "passive"))
      (node (ref "R26") (pin "2") (pinfunction "2_2") (pintype "passive"))
      (node (ref "R3") (pin "2") (pinfunction "2_2") (pintype "passive"))
      (node (ref "R35") (pin "2") (pinfunction "2_2") (pintype "passive"))
      (node (ref "R4") (pin "2") (pinfunction "2_2") (pintype "passive"))
      (node (ref "R5") (pin "2") (pinfunction "2_2") (pintype "passive"))
      (node (ref "R7") (pin "2") (pinfunction "2_2") (pintype "passive"))
      (node (ref "R81") (pin "1") (pinfunction "1_1") (pintype "passive"))
      (node (ref "R85") (pin "2") (pinfunction "2_2") (pintype "passive"))
      (node (ref "SD1") (pin "4") (pinfunction "VDD_4") (pintype "bidirectional"))
      (node (ref "U1") (pin "1") (pinfunction "VDDIO_1") (pintype "bidirectional"))
      (node (ref "U1") (pin "10") (pinfunction "VDDIO_10") (pintype "bidirectional"))
      (node (ref "U1") (pin "22") (pinfunction "VDDIO_22") (pintype "bidirectional"))
      (node (ref "U1") (pin "33") (pinfunction "VDDIO_33") (pintype "bidirectional"))
      (node (ref "U1") (pin "42") (pinfunction "VDDIO_42") (pintype "bidirectional"))
      (node (ref "U1") (pin "44") (pinfunction "LDO_IN_44") (pintype "bidirectional"))
      (node (ref "U1") (pin "48") (pinfunction "USB_VDD_48") (pintype "bidirectional"))
      (node (ref "U1") (pin "49") (pinfunction "VDDIO_49") (pintype "bidirectional"))
      (node (ref "U2") (pin "8") (pinfunction "VCC_8") (pintype "bidirectional"))
      (node (ref "U3") (pin "1") (pinfunction "VCC_1") (pintype "bidirectional"))
      (node (ref "U3") (pin "10") (pinfunction "IOVDD_10") (pintype "bidirectional"))
      (node (ref "U3") (pin "9") (pinfunction "VREF_9") (pintype "bidirectional"))
      (node (ref "U7") (pin "10") (pinfunction "V3_10") (pintype "bidirectional"))
      (node (ref "U7") (pin "7") (pinfunction "VCC_7") (pintype "bidirectional"))
    )
    (net (code "3") (name "+5V_UART0") (class "Default")
      (node (ref "D4") (pin "1") (pinfunction "1_1") (pintype "bidirectional"))
      (node (ref "D8") (pin "1") (pinfunction "1_1") (pintype "bidirectional"))
      (node (ref "J15") (pin "A4") (pinfunction "VBUS_A4") (pintype "bidirectional"))
      (node (ref "J15") (pin "A9") (pinfunction "VBUS_A9") (pintype "bidirectional"))
      (node (ref "J15") (pin "B4") (pinfunction "VBUS_B4") (pintype "bidirectional"))
      (node (ref "J15") (pin "B9") (pinfunction "VBUS_B9") (pintype "bidirectional"))
      (node (ref "P26") (pin "P$1") (pinfunction "P$1_P$1") (pintype "bidirectional"))
    )
    (net (code "4") (name "+5V_USB") (class "Default")
      (node (ref "D5") (pin "1") (pinfunction "1_1") (pintype "bidirectional"))
      (node (ref "D6") (pin "1") (pinfunction "1_1") (pintype "bidirectional"))
      (node (ref "J14") (pin "A4") (pinfunction "VBUS_A4") (pintype "bidirectional"))
      (node (ref "J14") (pin "A9") (pinfunction "VBUS_A9") (pintype "bidirectional"))
      (node (ref "J14") (pin "B4") (pinfunction "VBUS_B4") (pintype "bidirectional"))
      (node (ref "J14") (pin "B9") (pinfunction "VBUS_B9") (pintype "bidirectional"))
      (node (ref "P2") (pin "P$1") (pinfunction "P$1_P$1") (pintype "bidirectional"))
    )
    (net (code "5") (name "/CHG_LED") (class "Default")
      (node (ref "D15") (pin "-") (pinfunction "-_-") (pintype "passive"))
      (node (ref "U5") (pin "1") (pinfunction "GHRG_1") (pintype "bidirectional"))
    )
    (net (code "6") (name "/VIN") (class "Default")
      (node (ref "C31") (pin "2") (pinfunction "2_2") (pintype "passive"))
      (node (ref "C32") (pin "1") (pinfunction "1_1") (pintype "passive"))
      (node (ref "D2") (pin "-") (pinfunction "2_-") (pintype "bidirectional"))
      (node (ref "D6") (pin "2") (pinfunction "2_2") (pintype "bidirectional"))
      (node (ref "D8") (pin "2") (pinfunction "2_2") (pintype "bidirectional"))
      (node (ref "Q19") (pin "2") (pinfunction "S_2") (pintype "bidirectional"))
      (node (ref "U6") (pin "1") (pinfunction "EN_1") (pintype "bidirectional"))
      (node (ref "U6") (pin "4") (pinfunction "VIN_4") (pintype "bidirectional"))
    )
    (net (code "7") (name "AVDD") (class "Default")
      (node (ref "C3") (pin "1") (pinfunction "1_1") (pintype "passive"))
      (node (ref "R5") (pin "1") (pinfunction "1_1") (pintype "passive"))
      (node (ref "U1") (pin "43") (pinfunction "ADC_VDD_43") (pintype "bidirectional"))
    )
    (net (code "8") (name "BAT+") (class "Default")
      (node (ref "C19") (pin "2") (pinfunction "2_2") (pintype "passive"))
      (node (ref "D2") (pin "+") (pinfunction "1_+") (pintype "bidirectional"))
      (node (ref "J16") (pin "P$1") (pinfunction "P$1_P$1") (pintype "bidirectional"))
      (node (ref "P7") (pin "P$1") (pinfunction "P$1_P$1") (pintype "bidirectional"))
      (node (ref "Q19") (pin "3") (pinfunction "D_3") (pintype "bidirectional"))
      (node (ref "R20") (pin "1") (pinfunction "1_1") (pintype "passive"))
      (node (ref "U5") (pin "3") (pinfunction "BAT_3") (pintype "bidirectional"))
    )
    (net (code "9") (name "BOOT") (class "Default")
      (node (ref "R6") (pin "2") (pinfunction "2_2") (pintype "passive"))
      (node (ref "SW2") (pin "2") (pinfunction "2_2") (pintype "bidirectional"))
    )
    (net (code "10") (name "GND") (class "Default")
      (node (ref "C1") (pin "2") (pinfunction "2_2") (pintype "passive"))
      (node (ref "C10") (pin "2") (pinfunction "2_2") (pintype "passive"))
      (node (ref "C11") (pin "2") (pinfunction "2_2") (pintype "passive"))
      (node (ref "C12") (pin "2") (pinfunction "2_2") (pintype "passive"))
      (node (ref "C13") (pin "2") (pinfunction "2_2") (pintype "passive"))
      (node (ref "C14") (pin "2") (pinfunction "2_2") (pintype "passive"))
      (node (ref "C15") (pin "1") (pinfunction "1_1") (pintype "passive"))
      (node (ref "C16") (pin "2") (pinfunction "2_2") (pintype "passive"))
      (node (ref "C17") (pin "2") (pinfunction "2_2") (pintype "passive"))
      (node (ref "C18") (pin "1") (pinfunction "1_1") (pintype "passive"))
      (node (ref "C19") (pin "1") (pinfunction "1_1") (pintype "passive"))
      (node (ref "C2") (pin "1") (pinfunction "1_1") (pintype "passive"))
      (node (ref "C20") (pin "2") (pinfunction "2_2") (pintype "passive"))
      (node (ref "C21") (pin "2") (pinfunction "2_2") (pintype "passive"))
      (node (ref "C22") (pin "1") (pinfunction "1_1") (pintype "bidirectional"))
      (node (ref "C23") (pin "2") (pinfunction "2_2") (pintype "passive"))
      (node (ref "C28") (pin "1") (pinfunction "1_1") (pintype "passive"))
      (node (ref "C3") (pin "2") (pinfunction "2_2") (pintype "passive"))
      (node (ref "C30") (pin "1") (pinfunction "1_1") (pintype "passive"))
      (node (ref "C31") (pin "1") (pinfunction "1_1") (pintype "passive"))
      (node (ref "C32") (pin "2") (pinfunction "2_2") (pintype "passive"))
      (node (ref "C33") (pin "1") (pinfunction "1_1") (pintype "passive"))
      (node (ref "C35") (pin "2") (pinfunction "2_2") (pintype "passive"))
      (node (ref "C38") (pin "1") (pinfunction "1_1") (pintype "passive"))
      (node (ref "C39") (pin "1") (pinfunction "1_1") (pintype "passive"))
      (node (ref "C4") (pin "2") (pinfunction "2_2") (pintype "passive"))
      (node (ref "C40") (pin "1") (pinfunction "1_1") (pintype "passive"))
      (node (ref "C42") (pin "1") (pinfunction "1_1") (pintype "passive"))
      (node (ref "C43") (pin "2") (pinfunction "2_2") (pintype "passive"))
      (node (ref "C5") (pin "2") (pinfunction "2_2") (pintype "passive"))
      (node (ref "C6") (pin "2") (pinfunction "2_2") (pintype "passive"))
      (node (ref "C7") (pin "2") (pinfunction "2_2") (pintype "passive"))
      (node (ref "C8") (pin "2") (pinfunction "2_2") (pintype "passive"))
      (node (ref "C9") (pin "2") (pinfunction "2_2") (pintype "passive"))
      (node (ref "D3") (pin "-") (pinfunction "-_-") (pintype "passive"))
      (node (ref "J1") (pin "4") (pinfunction "4_4") (pintype "bidirectional"))
      (node (ref "J1") (pin "SS1") (pinfunction "SS1_SS1") (pintype "bidirectional"))
      (node (ref "J1") (pin "SS2") (pinfunction "SS2_SS2") (pintype "bidirectional"))
      (node (ref "J14") (pin "A1") (pinfunction "GND_A1") (pintype "bidirectional"))
      (node (ref "J14") (pin "A12") (pinfunction "GND_A12") (pintype "bidirectional"))
      (node (ref "J14") (pin "B1") (pinfunction "GND_B1") (pintype "bidirectional"))
      (node (ref "J14") (pin "B12") (pinfunction "GND_B12") (pintype "bidirectional"))
      (node (ref "J14") (pin "P$6") (pinfunction "P$17_P$6") (pintype "bidirectional"))
      (node (ref "J14") (pin "P$7") (pinfunction "P$18_P$7") (pintype "bidirectional"))
      (node (ref "J14") (pin "P$8") (pinfunction "P$19_P$8") (pintype "bidirectional"))
      (node (ref "J14") (pin "P$9") (pinfunction "P$20_P$9") (pintype "bidirectional"))
      (node (ref "J15") (pin "A1") (pinfunction "GND_A1") (pintype "bidirectional"))
      (node (ref "J15") (pin "A12") (pinfunction "GND_A12") (pintype "bidirectional"))
      (node (ref "J15") (pin "B1") (pinfunction "GND_B1") (pintype "bidirectional"))
      (node (ref "J15") (pin "B12") (pinfunction "GND_B12") (pintype "bidirectional"))
      (node (ref "J15") (pin "P$6") (pinfunction "P$17_P$6") (pintype "bidirectional"))
      (node (ref "J15") (pin "P$7") (pinfunction "P$18_P$7") (pintype "bidirectional"))
      (node (ref "J15") (pin "P$8") (pinfunction "P$19_P$8") (pintype "bidirectional"))
      (node (ref "J15") (pin "P$9") (pinfunction "P$20_P$9") (pintype "bidirectional"))
      (node (ref "J16") (pin "P$2") (pinfunction "P$2_P$2") (pintype "bidirectional"))
      (node (ref "J16") (pin "P$3") (pinfunction "P$3_P$3") (pintype "bidirectional"))
      (node (ref "J16") (pin "P$4") (pinfunction "P$4_P$4") (pintype "bidirectional"))
      (node (ref "J17") (pin "P$1") (pinfunction "GND_P$1") (pintype "bidirectional"))
      (node (ref "J17") (pin "P$8") (pinfunction "GND2_P$8") (pintype "bidirectional"))
      (node (ref "J2") (pin "15") (pinfunction "P$15_15") (pintype "bidirectional"))
      (node (ref "J6") (pin "4") (pinfunction "4_4") (pintype "bidirectional"))
      (node (ref "J6") (pin "SS1") (pinfunction "SS1_SS1") (pintype "bidirectional"))
      (node (ref "J6") (pin "SS2") (pinfunction "SS2_SS2") (pintype "bidirectional"))
      (node (ref "P1") (pin "P$1") (pinfunction "P$1_P$1") (pintype "bidirectional"))
      (node (ref "P14") (pin "P$1") (pinfunction "P$1_P$1") (pintype "bidirectional"))
      (node (ref "P21") (pin "P$1") (pinfunction "P$1_P$1") (pintype "bidirectional"))
      (node (ref "P25") (pin "P$1") (pinfunction "P$1_P$1") (pintype "bidirectional"))
      (node (ref "P29") (pin "P$1") (pinfunction "P$1_P$1") (pintype "bidirectional"))
      (node (ref "P42") (pin "P$1") (pinfunction "P$1_P$1") (pintype "bidirectional"))
      (node (ref "P59") (pin "P$1") (pinfunction "P$1_P$1") (pintype "bidirectional"))
      (node (ref "P6") (pin "P$1") (pinfunction "P$1_P$1") (pintype "bidirectional"))
      (node (ref "P9") (pin "P$1") (pinfunction "P$1_P$1") (pintype "bidirectional"))
      (node (ref "Q1") (pin "2") (pinfunction "S_2") (pintype "bidirectional"))
      (node (ref "Q2") (pin "2") (pinfunction "S_2") (pintype "bidirectional"))
      (node (ref "R12") (pin "2") (pinfunction "2_2") (pintype "passive"))
      (node (ref "R13") (pin "1") (pinfunction "1_1") (pintype "passive"))
      (node (ref "R14") (pin "1") (pinfunction "1_1") (pintype "passive"))
      (node (ref "R19") (pin "2") (pinfunction "2_2") (pintype "passive"))
      (node (ref "R66") (pin "1") (pinfunction "1_1") (pintype "passive"))
      (node (ref "R68") (pin "2") (pinfunction "2_2") (pintype "passive"))
      (node (ref "R69") (pin "1") (pinfunction "1_1") (pintype "passive"))
      (node (ref "R8") (pin "1") (pinfunction "1_1") (pintype "passive"))
      (node (ref "R82") (pin "1") (pinfunction "1_1") (pintype "passive"))
      (node (ref "R84") (pin "2") (pinfunction "2_2") (pintype "passive"))
      (node (ref "SD1") (pin "6") (pinfunction "VSS_6") (pintype "bidirectional"))
      (node (ref "SD1") (pin "G1") (pinfunction "G1_G1") (pintype "bidirectional"))
      (node (ref "SD1") (pin "G2") (pinfunction "G2_G2") (pintype "bidirectional"))
      (node (ref "SD1") (pin "G3") (pinfunction "G3_G3") (pintype "bidirectional"))
      (node (ref "SD1") (pin "G4") (pinfunction "G4_G4") (pintype "bidirectional"))
      (node (ref "SW1") (pin "1") (pinfunction "1_1") (pintype "bidirectional"))
      (node (ref "SW2") (pin "1") (pinfunction "1_1") (pintype "bidirectional"))
      (node (ref "T1") (pin "1") (pinfunction "P$1_1") (pintype "bidirectional"))
      (node (ref "T2") (pin "1") (pinfunction "P$1_1") (pintype "bidirectional"))
      (node (ref "T3") (pin "1") (pinfunction "P$1_1") (pintype "bidirectional"))
      (node (ref "T4") (pin "1") (pinfunction "P$1_1") (pintype "bidirectional"))
      (node (ref "U1") (pin "19") (pinfunction "TESTEN_19") (pintype "bidirectional"))
      (node (ref "U1") (pin "EPAD") (pinfunction "GND_EPAD") (pintype "bidirectional"))
      (node (ref "U2") (pin "4") (pinfunction "GND_4") (pintype "bidirectional"))
      (node (ref "U3") (pin "6") (pinfunction "GND_6") (pintype "bidirectional"))
      (node (ref "U5") (pin "2") (pinfunction "GND_2") (pintype "bidirectional"))
      (node (ref "U6") (pin "2") (pinfunction "GND_2") (pintype "bidirectional"))
      (node (ref "U7") (pin "3") (pinfunction "GND_3") (pintype "bidirectional"))
      (node (ref "X1") (pin "2") (pinfunction "GND_2") (pintype "bidirectional"))
      (node (ref "X1") (pin "4") (pinfunction "GND_4") (pintype "bidirectional"))
    )
    (net (code "11") (name "GP0{slash}UART0_TX") (class "Default")
      (node (ref "J2") (pin "1") (pinfunction "P$1_1") (pintype "bidirectional"))
      (node (ref "P8") (pin "P$1") (pinfunction "P$1_P$1") (pintype "bidirectional"))
      (node (ref "R70") (pin "2") (pinfunction "2_2") (pintype "passive"))
      (node (ref "U1") (pin "2") (pinfunction "GPIO0_2") (pintype "bidirectional"))
    )
    (net (code "12") (name "GP1{slash}UART0_RX") (class "Default")
      (node (ref "J2") (pin "2") (pinfunction "P$2_2") (pintype "bidirectional"))
      (node (ref "P17") (pin "P$1") (pinfunction "P$1_P$1") (pintype "bidirectional"))
      (node (ref "R83") (pin "2") (pinfunction "2_2") (pintype "passive"))
      (node (ref "U1") (pin "3") (pinfunction "GPIO1_3") (pintype "bidirectional"))
    )
    (net (code "13") (name "GP2{slash}I2C1_SDA") (class "Default")
      (node (ref "J2") (pin "3") (pinfunction "P$3_3") (pintype "bidirectional"))
      (node (ref "P18") (pin "P$1") (pinfunction "P$1_P$1") (pintype "bidirectional"))
      (node (ref "U1") (pin "4") (pinfunction "GPIO2_4") (pintype "bidirectional"))
    )
    (net (code "14") (name "GP3{slash}I2C1_SCL") (class "Default")
      (node (ref "J2") (pin "4") (pinfunction "P$4_4") (pintype "bidirectional"))
      (node (ref "P19") (pin "P$1") (pinfunction "P$1_P$1") (pintype "bidirectional"))
      (node (ref "U1") (pin "5") (pinfunction "GPIO3_5") (pintype "bidirectional"))
    )
    (net (code "15") (name "GP4{slash}UART1_TX") (class "Default")
      (node (ref "J1") (pin "2") (pinfunction "2_2") (pintype "bidirectional"))
      (node (ref "J2") (pin "5") (pinfunction "P$5_5") (pintype "bidirectional"))
      (node (ref "P20") (pin "P$1") (pinfunction "P$1_P$1") (pintype "bidirectional"))
      (node (ref "P23") (pin "P$1") (pinfunction "P$1_P$1") (pintype "bidirectional"))
      (node (ref "U1") (pin "6") (pinfunction "GPIO4_6") (pintype "bidirectional"))
    )
    (net (code "16") (name "GP5{slash}UART1_RX") (class "Default")
      (node (ref "J1") (pin "1") (pinfunction "1_1") (pintype "bidirectional"))
      (node (ref "J2") (pin "6") (pinfunction "P$6_6") (pintype "bidirectional"))
      (node (ref "P24") (pin "P$1") (pinfunction "P$1_P$1") (pintype "bidirectional"))
      (node (ref "P50") (pin "P$1") (pinfunction "P$1_P$1") (pintype "bidirectional"))
      (node (ref "U1") (pin "7") (pinfunction "GPIO5_7") (pintype "bidirectional"))
    )
    (net (code "17") (name "GP6*I2C1_SDA") (class "Default")
      (node (ref "J2") (pin "7") (pinfunction "P$7_7") (pintype "bidirectional"))
      (node (ref "P51") (pin "P$1") (pinfunction "P$1_P$1") (pintype "bidirectional"))
      (node (ref "U1") (pin "8") (pinfunction "GPIO6_8") (pintype "bidirectional"))
    )
    (net (code "18") (name "GP7*I2C1_SCL") (class "Default")
      (node (ref "J2") (pin "8") (pinfunction "P$8_8") (pintype "bidirectional"))
      (node (ref "P52") (pin "P$1") (pinfunction "P$1_P$1") (pintype "bidirectional"))
      (node (ref "U1") (pin "9") (pinfunction "GPIO7_9") (pintype "bidirectional"))
    )
    (net (code "19") (name "GP8{slash}LCD_DC") (class "Default")
      (node (ref "J17") (pin "P$4") (pinfunction "D/C_P$4") (pintype "bidirectional"))
      (node (ref "P34") (pin "P$1") (pinfunction "P$1_P$1") (pintype "bidirectional"))
      (node (ref "U1") (pin "11") (pinfunction "GPIO8_11") (pintype "bidirectional"))
    )
    (net (code "20") (name "GP9{slash}LCD_CS{slash}SPI_CS0") (class "Default")
      (node (ref "J17") (pin "P$5") (pinfunction "CS_P$5") (pintype "bidirectional"))
      (node (ref "P35") (pin "P$1") (pinfunction "P$1_P$1") (pintype "bidirectional"))
      (node (ref "U1") (pin "12") (pinfunction "GPIO9_12") (pintype "bidirectional"))
    )
    (net (code "21") (name "GP10{slash}SPI_CLK{slash}LCD_CLK{slash}TP_CLK{slash}SD_CLK") (class "Default")
      (node (ref "J17") (pin "P$3") (pinfunction "SCL_P$3") (pintype "bidirectional"))
      (node (ref "P32") (pin "P$1") (pinfunction "P$1_P$1") (pintype "bidirectional"))
      (node (ref "P45") (pin "P$1") (pinfunction "P$1_P$1") (pintype "bidirectional"))
      (node (ref "R103") (pin "1") (pinfunction "1_1") (pintype "passive"))
      (node (ref "SD1") (pin "5") (pinfunction "SCLK_5") (pintype "bidirectional"))
      (node (ref "U1") (pin "13") (pinfunction "GPIO10_13") (pintype "bidirectional"))
      (node (ref "U3") (pin "16") (pinfunction "DCLK_16") (pintype "bidirectional"))
    )
    (net (code "22") (name "GP11{slash}SPI_MOSI{slash}LCD_SDI{slash}TP_SDI{slash}SD_SDI") (class "Default")
      (node (ref "J17") (pin "P$6") (pinfunction "SDA_P$6") (pintype "bidirectional"))
      (node (ref "P36") (pin "P$1") (pinfunction "P$1_P$1") (pintype "bidirectional"))
      (node (ref "P44") (pin "P$1") (pinfunction "P$1_P$1") (pintype "bidirectional"))
      (node (ref "R104") (pin "1") (pinfunction "1_1") (pintype "passive"))
      (node (ref "R112") (pin "2") (pinfunction "2_2") (pintype "passive"))
      (node (ref "SD1") (pin "3") (pinfunction "DI_3") (pintype "bidirectional"))
      (node (ref "U1") (pin "14") (pinfunction "GPIO11_14") (pintype "bidirectional"))
      (node (ref "U3") (pin "14") (pinfunction "DIN_14") (pintype "bidirectional"))
    )
    (net (code "23") (name "GP12{slash}SPI_MISO{slash}LCD_SDO{slash}TP_SDO{slash}SD_SDO") (class "Default")
      (node (ref "P46") (pin "P$1") (pinfunction "P$1_P$1") (pintype "bidirectional"))
      (node (ref "R113") (pin "2") (pinfunction "2_2") (pintype "passive"))
      (node (ref "SD1") (pin "7") (pinfunction "DO_7") (pintype "bidirectional"))
      (node (ref "U1") (pin "15") (pinfunction "GPIO12_15") (pintype "bidirectional"))
      (node (ref "U3") (pin "12") (pinfunction "DOUT_12") (pintype "bidirectional"))
    )
    (net (code "24") (name "GP13{slash}LCD_BL") (class "Default")
      (node (ref "U1") (pin "16") (pinfunction "GPIO13_16") (pintype "bidirectional"))
    )
    (net (code "25") (name "GP14{slash}BUZZER") (class "Default")
      (node (ref "Q2") (pin "1") (pinfunction "G_1") (pintype "bidirectional"))
      (node (ref "R14") (pin "2") (pinfunction "2_2") (pintype "passive"))
      (node (ref "U1") (pin "17") (pinfunction "GPIO14_17") (pintype "bidirectional"))
    )
    (net (code "26") (name "GP15{slash}LCD_RST") (class "Default")
      (node (ref "J17") (pin "P$2") (pinfunction "RESET_P$2") (pintype "bidirectional"))
      (node (ref "P31") (pin "P$1") (pinfunction "P$1_P$1") (pintype "bidirectional"))
      (node (ref "U1") (pin "18") (pinfunction "GPIO15_18") (pintype "bidirectional"))
    )
    (net (code "27") (name "GP16{slash}TP_CS{slash}SPI_CS1") (class "Default")
      (node (ref "U1") (pin "27") (pinfunction "GPIO16_27") (pintype "bidirectional"))
      (node (ref "U3") (pin "15") (pinfunction "CS_15") (pintype "bidirectional"))
    )
    (net (code "28") (name "GP17{slash}TP_IRQ") (class "Default")
      (node (ref "R105") (pin "1") (pinfunction "1_1") (pintype "passive"))
      (node (ref "U1") (pin "28") (pinfunction "GPIO17_28") (pintype "bidirectional"))
      (node (ref "U3") (pin "11") (pinfunction "PENIRQ_11") (pintype "bidirectional"))
    )
    (net (code "29") (name "GP18{slash}LCD_BL_PWM") (class "Default")
      (node (ref "Q1") (pin "1") (pinfunction "G_1") (pintype "bidirectional"))
      (node (ref "R8") (pin "2") (pinfunction "2_2") (pintype "passive"))
      (node (ref "U1") (pin "29") (pinfunction "GPIO18_29") (pintype "bidirectional"))
    )
    (net (code "30") (name "GP19*") (class "Default")
      (node (ref "J2") (pin "9") (pinfunction "P$9_9") (pintype "bidirectional"))
      (node (ref "P53") (pin "P$1") (pinfunction "P$1_P$1") (pintype "bidirectional"))
      (node (ref "U1") (pin "30") (pinfunction "GPIO19_30") (pintype "bidirectional"))
    )
    (net (code "31") (name "GP20{slash}I2C0_SDA") (class "Default")
      (node (ref "J2") (pin "10") (pinfunction "P$10_10") (pintype "bidirectional"))
      (node (ref "J6") (pin "2") (pinfunction "2_2") (pintype "bidirectional"))
      (node (ref "P15") (pin "P$1") (pinfunction "P$1_P$1") (pintype "bidirectional"))
      (node (ref "P54") (pin "P$1") (pinfunction "P$1_P$1") (pintype "bidirectional"))
      (node (ref "R3") (pin "1") (pinfunction "1_1") (pintype "passive"))
      (node (ref "U1") (pin "31") (pinfunction "GPIO20_31") (pintype "bidirectional"))
    )
    (net (code "32") (name "GP21{slash}I2C0_SCL") (class "Default")
      (node (ref "J2") (pin "11") (pinfunction "P$11_11") (pintype "bidirectional"))
      (node (ref "J6") (pin "1") (pinfunction "1_1") (pintype "bidirectional"))
      (node (ref "P16") (pin "P$1") (pinfunction "P$1_P$1") (pintype "bidirectional"))
      (node (ref "P55") (pin "P$1") (pinfunction "P$1_P$1") (pintype "bidirectional"))
      (node (ref "R26") (pin "1") (pinfunction "1_1") (pintype "passive"))
      (node (ref "U1") (pin "32") (pinfunction "GPIO21_32") (pintype "bidirectional"))
    )
    (net (code "33") (name "GP22{slash}SD_CS{slash}SPI_CS2") (class "Default")
      (node (ref "P47") (pin "P$1") (pinfunction "P$1_P$1") (pintype "bidirectional"))
      (node (ref "R109") (pin "2") (pinfunction "2_2") (pintype "passive"))
      (node (ref "SD1") (pin "2") (pinfunction "CS_2") (pintype "bidirectional"))
      (node (ref "U1") (pin "34") (pinfunction "GPIO22_34") (pintype "bidirectional"))
    )
    (net (code "34") (name "GP23*") (class "Default")
      (node (ref "U1") (pin "35") (pinfunction "GPIO23_35") (pintype "bidirectional"))
    )
    (net (code "35") (name "GP24*") (class "Default")
      (node (ref "U1") (pin "36") (pinfunction "GPIO24_36") (pintype "bidirectional"))
    )
    (net (code "36") (name "GP25{slash}LED") (class "Default")
      (node (ref "U1") (pin "37") (pinfunction "GPIO25_37") (pintype "bidirectional"))
    )
    (net (code "37") (name "GP26*ADC0*I2C1_SDA") (class "Default")
      (node (ref "J2") (pin "12") (pinfunction "P$12_12") (pintype "bidirectional"))
      (node (ref "P56") (pin "P$1") (pinfunction "P$1_P$1") (pintype "bidirectional"))
      (node (ref "U1") (pin "38") (pinfunction "GPIO26/ADC0_38") (pintype "bidirectional"))
    )
    (net (code "38") (name "GP27*ADC1*I2C1_SCL") (class "Default")
      (node (ref "J2") (pin "13") (pinfunction "P$13_13") (pintype "bidirectional"))
      (node (ref "P57") (pin "P$1") (pinfunction "P$1_P$1") (pintype "bidirectional"))
      (node (ref "U1") (pin "39") (pinfunction "GPIO27/ADC1_39") (pintype "bidirectional"))
    )
    (net (code "39") (name "GP28*ADC2") (class "Default")
      (node (ref "J2") (pin "14") (pinfunction "P$14_14") (pintype "bidirectional"))
      (node (ref "P58") (pin "P$1") (pinfunction "P$1_P$1") (pintype "bidirectional"))
      (node (ref "U1") (pin "40") (pinfunction "GPIO28/ADC2_40") (pintype "bidirectional"))
    )
    (net (code "40") (name "GP29{slash}BAT+_ADC3") (class "Default")
      (node (ref "R19") (pin "1") (pinfunction "1_1") (pintype "passive"))
      (node (ref "R20") (pin "2") (pinfunction "2_2") (pintype "passive"))
      (node (ref "U1") (pin "41") (pinfunction "GPIO29/ADC3_41") (pintype "bidirectional"))
    )
    (net (code "41") (name "LED-A") (class "Default")
      (node (ref "J17") (pin "P$10") (pinfunction "LED-A_P$10") (pintype "bidirectional"))
      (node (ref "P5") (pin "P$1") (pinfunction "P$1_P$1") (pintype "bidirectional"))
      (node (ref "R10") (pin "1") (pinfunction "1_1") (pintype "passive"))
    )
    (net (code "42") (name "LED-K") (class "Default")
      (node (ref "J17") (pin "P$11") (pinfunction "LED-K_P$11") (pintype "bidirectional"))
      (node (ref "J17") (pin "P$12") (pinfunction "LED-K2_P$12") (pintype "bidirectional"))
      (node (ref "J17") (pin "P$13") (pinfunction "LED-K3_P$13") (pintype "bidirectional"))
      (node (ref "J17") (pin "P$14") (pinfunction "LED-K4_P$14") (pintype "bidirectional"))
      (node (ref "P41") (pin "P$1") (pinfunction "P$1_P$1") (pintype "bidirectional"))
      (node (ref "R9") (pin "2") (pinfunction "2_2") (pintype "passive"))
    )
    (net (code "43") (name "Net-(B1-+)") (class "Default")
      (node (ref "B1") (pin "1") (pinfunction "+_1") (pintype "bidirectional"))
      (node (ref "D1") (pin "-") (pinfunction "2_-") (pintype "bidirectional"))
      (node (ref "R4") (pin "1") (pinfunction "1_1") (pintype "passive"))
    )
    (net (code "44") (name "Net-(B1--)") (class "Default")
      (node (ref "B1") (pin "2") (pinfunction "-_2") (pintype "bidirectional"))
      (node (ref "D1") (pin "+") (pinfunction "1_+") (pintype "bidirectional"))
      (node (ref "Q2") (pin "3") (pinfunction "D_3") (pintype "bidirectional"))
    )
    (net (code "45") (name "Net-(D3-Pad+)") (class "Default")
      (node (ref "D3") (pin "+") (pinfunction "+_+") (pintype "passive"))
      (node (ref "R35") (pin "1") (pinfunction "1_1") (pintype "passive"))
    )
    (net (code "46") (name "Net-(D15-Pad+)") (class "Default")
      (node (ref "D15") (pin "+") (pinfunction "+_+") (pintype "passive"))
      (node (ref "R85") (pin "1") (pinfunction "1_1") (pintype "passive"))
    )
    (net (code "47") (name "Net-(J14-CC1)") (class "Default")
      (node (ref "J14") (pin "A5") (pinfunction "CC1_A5") (pintype "bidirectional"))
      (node (ref "R13") (pin "2") (pinfunction "2_2") (pintype "passive"))
    )
    (net (code "48") (name "Net-(J14-CC2)") (class "Default")
      (node (ref "J14") (pin "B5") (pinfunction "CC2_B5") (pintype "bidirectional"))
      (node (ref "R12") (pin "1") (pinfunction "1_1") (pintype "passive"))
    )
    (net (code "49") (name "Net-(J15-CC1)") (class "Default")
      (node (ref "J15") (pin "A5") (pinfunction "CC1_A5") (pintype "bidirectional"))
      (node (ref "R69") (pin "2") (pinfunction "2_2") (pintype "passive"))
    )
    (net (code "50") (name "Net-(J15-CC2)") (class "Default")
      (node (ref "J15") (pin "B5") (pinfunction "CC2_B5") (pintype "bidirectional"))
      (node (ref "R68") (pin "1") (pinfunction "1_1") (pintype "passive"))
    )
    (net (code "51") (name "Net-(Q1-D)") (class "Default")
      (node (ref "Q1") (pin "3") (pinfunction "D_3") (pintype "bidirectional"))
      (node (ref "R9") (pin "1") (pinfunction "1_1") (pintype "passive"))
    )
    (net (code "52") (name "Net-(SD1-DATA1)") (class "Default")
      (node (ref "R111") (pin "2") (pinfunction "2_2") (pintype "passive"))
      (node (ref "SD1") (pin "8") (pinfunction "DATA1_8") (pintype "bidirectional"))
    )
    (net (code "53") (name "Net-(SD1-DATA2)") (class "Default")
      (node (ref "R110") (pin "2") (pinfunction "2_2") (pintype "passive"))
      (node (ref "SD1") (pin "1") (pinfunction "DATA2_1") (pintype "bidirectional"))
    )
    (net (code "54") (name "Net-(U1-XIN)") (class "Default")
      (node (ref "C1") (pin "1") (pinfunction "1_1") (pintype "passive"))
      (node (ref "U1") (pin "20") (pinfunction "XIN_20") (pintype "bidirectional"))
      (node (ref "X1") (pin "1") (pinfunction "XIN_1") (pintype "bidirectional"))
    )
    (net (code "55") (name "Net-(U1-XOUT)") (class "Default")
      (node (ref "R2") (pin "2") (pinfunction "2_2") (pintype "passive"))
      (node (ref "U1") (pin "21") (pinfunction "XOUT_21") (pintype "bidirectional"))
    )
    (net (code "56") (name "Net-(U3-VBAT)") (class "Default")
      (node (ref "R106") (pin "2") (pinfunction "2_2") (pintype "passive"))
      (node (ref "U3") (pin "7") (pinfunction "VBAT_7") (pintype "bidirectional"))
    )
    (net (code "57") (name "Net-(U5-PROG)") (class "Default")
      (node (ref "R84") (pin "1") (pinfunction "1_1") (pintype "passive"))
      (node (ref "U5") (pin "5") (pinfunction "PROG_5") (pintype "bidirectional"))
    )
    (net (code "58") (name "Net-(U6-FB)") (class "Default")
      (node (ref "R81") (pin "2") (pinfunction "2_2") (pintype "passive"))
      (node (ref "R82") (pin "2") (pinfunction "2_2") (pintype "passive"))
      (node (ref "U6") (pin "5") (pinfunction "FB_5") (pintype "bidirectional"))
    )
    (net (code "59") (name "Net-(U6-SW)") (class "Default")
      (node (ref "L2") (pin "1") (pinfunction "1_1") (pintype "bidirectional"))
      (node (ref "U6") (pin "3") (pinfunction "SW_3") (pintype "bidirectional"))
    )
    (net (code "60") (name "Net-(U7-RXD)") (class "Default")
      (node (ref "R70") (pin "1") (pinfunction "1_1") (pintype "passive"))
      (node (ref "U7") (pin "9") (pinfunction "RXD_9") (pintype "bidirectional"))
    )
    (net (code "61") (name "Net-(U7-TXD)") (class "Default")
      (node (ref "R83") (pin "1") (pinfunction "1_1") (pintype "passive"))
      (node (ref "U7") (pin "8") (pinfunction "TXD_8") (pintype "bidirectional"))
    )
    (net (code "62") (name "Net-(X1-XOUT)") (class "Default")
      (node (ref "C2") (pin "2") (pinfunction "2_2") (pintype "passive"))
      (node (ref "R2") (pin "1") (pinfunction "1_1") (pintype "passive"))
      (node (ref "X1") (pin "3") (pinfunction "XOUT_3") (pintype "bidirectional"))
    )
    (net (code "63") (name "QSPI_CS") (class "Default")
      (node (ref "R6") (pin "1") (pinfunction "1_1") (pintype "passive"))
      (node (ref "R7") (pin "1") (pinfunction "1_1") (pintype "passive"))
      (node (ref "U1") (pin "56") (pinfunction "QSPI_~{CS}_56") (pintype "bidirectional"))
      (node (ref "U2") (pin "1") (pinfunction "/CS_1") (pintype "bidirectional"))
    )
    (net (code "64") (name "QSPI_D0") (class "Default")
      (node (ref "U1") (pin "53") (pinfunction "QSPI_SD0_53") (pintype "bidirectional"))
      (node (ref "U2") (pin "5") (pinfunction "DI(IO0)_5") (pintype "bidirectional"))
    )
    (net (code "65") (name "QSPI_D1") (class "Default")
      (node (ref "U1") (pin "55") (pinfunction "QSPI_SD1_55") (pintype "bidirectional"))
      (node (ref "U2") (pin "2") (pinfunction "DO(IO1)_2") (pintype "bidirectional"))
    )
    (net (code "66") (name "QSPI_D2") (class "Default")
      (node (ref "U1") (pin "54") (pinfunction "QSPI_SD2_54") (pintype "bidirectional"))
      (node (ref "U2") (pin "3") (pinfunction "/WP(IO2)_3") (pintype "bidirectional"))
    )
    (net (code "67") (name "QSPI_D3") (class "Default")
      (node (ref "U1") (pin "51") (pinfunction "QSPI_SD3_51") (pintype "bidirectional"))
      (node (ref "U2") (pin "7") (pinfunction "/HOLD/RESET(IO3)_7") (pintype "bidirectional"))
    )
    (net (code "68") (name "QSPI_SCK") (class "Default")
      (node (ref "U1") (pin "52") (pinfunction "QSPI_SCLK_52") (pintype "bidirectional"))
      (node (ref "U2") (pin "6") (pinfunction "CLK_6") (pintype "bidirectional"))
    )
    (net (code "69") (name "RESET") (class "Default")
      (node (ref "C4") (pin "1") (pinfunction "1_1") (pintype "passive"))
      (node (ref "R1") (pin "1") (pinfunction "1_1") (pintype "passive"))
      (node (ref "SW1") (pin "2") (pinfunction "2_2") (pintype "bidirectional"))
      (node (ref "U1") (pin "26") (pinfunction "RUN_26") (pintype "bidirectional"))
    )
    (net (code "70") (name "SWCLK") (class "Default")
      (node (ref "P11") (pin "P$1") (pinfunction "P$1_P$1") (pintype "bidirectional"))
      (node (ref "U1") (pin "24") (pinfunction "SWCLK_24") (pintype "bidirectional"))
    )
    (net (code "71") (name "SWDIO") (class "Default")
      (node (ref "P12") (pin "P$1") (pinfunction "P$1_P$1") (pintype "bidirectional"))
      (node (ref "U1") (pin "25") (pinfunction "SWDIO_25") (pintype "bidirectional"))
    )
    (net (code "72") (name "TP_X+") (class "Default")
      (node (ref "C30") (pin "2") (pinfunction "2_2") (pintype "passive"))
      (node (ref "J17") (pin "P$15") (pinfunction "XL_P$15") (pintype "bidirectional"))
      (node (ref "P33") (pin "P$1") (pinfunction "P$1_P$1") (pintype "bidirectional"))
      (node (ref "U3") (pin "2") (pinfunction "XP_2") (pintype "bidirectional"))
    )
    (net (code "73") (name "TP_X-") (class "Default")
      (node (ref "C39") (pin "2") (pinfunction "2_2") (pintype "passive"))
      (node (ref "J17") (pin "P$17") (pinfunction "XR_P$17") (pintype "bidirectional"))
      (node (ref "P38") (pin "P$1") (pinfunction "P$1_P$1") (pintype "bidirectional"))
      (node (ref "U3") (pin "4") (pinfunction "XN_4") (pintype "bidirectional"))
    )
    (net (code "74") (name "TP_Y+") (class "Default")
      (node (ref "C38") (pin "2") (pinfunction "2_2") (pintype "passive"))
      (node (ref "J17") (pin "P$18") (pinfunction "YD_P$18") (pintype "bidirectional"))
      (node (ref "P39") (pin "P$1") (pinfunction "P$1_P$1") (pintype "bidirectional"))
      (node (ref "U3") (pin "3") (pinfunction "YP_3") (pintype "bidirectional"))
    )
    (net (code "75") (name "TP_Y-") (class "Default")
      (node (ref "C40") (pin "2") (pinfunction "2_2") (pintype "passive"))
      (node (ref "J17") (pin "P$16") (pinfunction "YU_P$16") (pintype "bidirectional"))
      (node (ref "P37") (pin "P$1") (pinfunction "P$1_P$1") (pintype "bidirectional"))
      (node (ref "U3") (pin "5") (pinfunction "YN_5") (pintype "bidirectional"))
    )
    (net (code "76") (name "UART_USB_D+") (class "Default")
      (node (ref "J15") (pin "A6") (pinfunction "DP1_A6") (pintype "bidirectional"))
      (node (ref "J15") (pin "B6") (pinfunction "DP2_B6") (pintype "bidirectional"))
      (node (ref "P27") (pin "P$1") (pinfunction "P$1_P$1") (pintype "bidirectional"))
      (node (ref "U7") (pin "1") (pinfunction "D+_1") (pintype "bidirectional"))
    )
    (net (code "77") (name "UART_USB_D-") (class "Default")
      (node (ref "J15") (pin "A7") (pinfunction "DN1_A7") (pintype "bidirectional"))
      (node (ref "J15") (pin "B7") (pinfunction "DN2_B7") (pintype "bidirectional"))
      (node (ref "P28") (pin "P$1") (pinfunction "P$1_P$1") (pintype "bidirectional"))
      (node (ref "U7") (pin "2") (pinfunction "D-_2") (pintype "bidirectional"))
    )
    (net (code "78") (name "USB_D+") (class "Default")
      (node (ref "J14") (pin "A6") (pinfunction "DP1_A6") (pintype "bidirectional"))
      (node (ref "J14") (pin "B6") (pinfunction "DP2_B6") (pintype "bidirectional"))
      (node (ref "P3") (pin "P$1") (pinfunction "P$1_P$1") (pintype "bidirectional"))
      (node (ref "U1") (pin "47") (pinfunction "USB_D+_47") (pintype "bidirectional"))
    )
    (net (code "79") (name "USB_D-") (class "Default")
      (node (ref "J14") (pin "A7") (pinfunction "DN1_A7") (pintype "bidirectional"))
      (node (ref "J14") (pin "B7") (pinfunction "DN2_B7") (pintype "bidirectional"))
      (node (ref "P4") (pin "P$1") (pinfunction "P$1_P$1") (pintype "bidirectional"))
      (node (ref "U1") (pin "46") (pinfunction "USB_D-_46") (pintype "bidirectional"))
    )
    (net (code "80") (name "VBAT_IN") (class "Default")
      (node (ref "C22") (pin "2") (pinfunction "2_2") (pintype "bidirectional"))
      (node (ref "C23") (pin "1") (pinfunction "1_1") (pintype "passive"))
      (node (ref "D4") (pin "2") (pinfunction "2_2") (pintype "bidirectional"))
      (node (ref "D5") (pin "2") (pinfunction "2_2") (pintype "bidirectional"))
      (node (ref "Q19") (pin "1") (pinfunction "G_1") (pintype "bidirectional"))
      (node (ref "R66") (pin "2") (pinfunction "2_2") (pintype "passive"))
      (node (ref "U5") (pin "4") (pinfunction "VCC_4") (pintype "bidirectional"))
    )
    (net (code "81") (name "unconnected-(J14-SBU1-PadA8)") (class "Default")
      (node (ref "J14") (pin "A8") (pinfunction "SBU1_A8") (pintype "bidirectional"))
    )
    (net (code "82") (name "unconnected-(J14-SBU2-PadB8)") (class "Default")
      (node (ref "J14") (pin "B8") (pinfunction "SBU2_B8") (pintype "bidirectional"))
    )
    (net (code "83") (name "unconnected-(J15-SBU1-PadA8)") (class "Default")
      (node (ref "J15") (pin "A8") (pinfunction "SBU1_A8") (pintype "bidirectional"))
    )
    (net (code "84") (name "unconnected-(J15-SBU2-PadB8)") (class "Default")
      (node (ref "J15") (pin "B8") (pinfunction "SBU2_B8") (pintype "bidirectional"))
    )
    (net (code "85") (name "unconnected-(J17-SDO-PadP$7)") (class "Default")
      (node (ref "J17") (pin "P$7") (pinfunction "SDO_P$7") (pintype "bidirectional"))
    )
    (net (code "86") (name "unconnected-(P48-PadP$1)") (class "Default")
      (node (ref "P48") (pin "P$1") (pinfunction "P$1_P$1") (pintype "bidirectional"))
    )
    (net (code "87") (name "unconnected-(P49-PadP$1)") (class "Default")
      (node (ref "P49") (pin "P$1") (pinfunction "P$1_P$1") (pintype "bidirectional"))
    )
    (net (code "88") (name "unconnected-(SD1-CDN-Pad9)") (class "Default")
      (node (ref "SD1") (pin "9") (pinfunction "CDN_9") (pintype "bidirectional"))
    )
    (net (code "89") (name "unconnected-(U3-BUESY-Pad13)") (class "Default")
      (node (ref "U3") (pin "13") (pinfunction "BUESY_13") (pintype "bidirectional"))
    )
    (net (code "90") (name "unconnected-(U3-IN-Pad8)") (class "Default")
      (node (ref "U3") (pin "8") (pinfunction "IN_8") (pintype "bidirectional"))
    )
    (net (code "91") (name "unconnected-(U7-CTS-Pad5)") (class "Default")
      (node (ref "U7") (pin "5") (pinfunction "CTS_5") (pintype "bidirectional"))
    )
    (net (code "92") (name "unconnected-(U7-RTS-Pad4)") (class "Default")
      (node (ref "U7") (pin "4") (pinfunction "RTS_4") (pintype "bidirectional"))
    )
    (net (code "93") (name "unconnected-(U7-TNOW-Pad6)") (class "Default")
      (node (ref "U7") (pin "6") (pinfunction "TNOW_6") (pintype "bidirectional"))
    )
  )
)
